# NB-IoT-ideaboard-v2_0.net
KiCad netlist of a schematic drawn in EAGLE
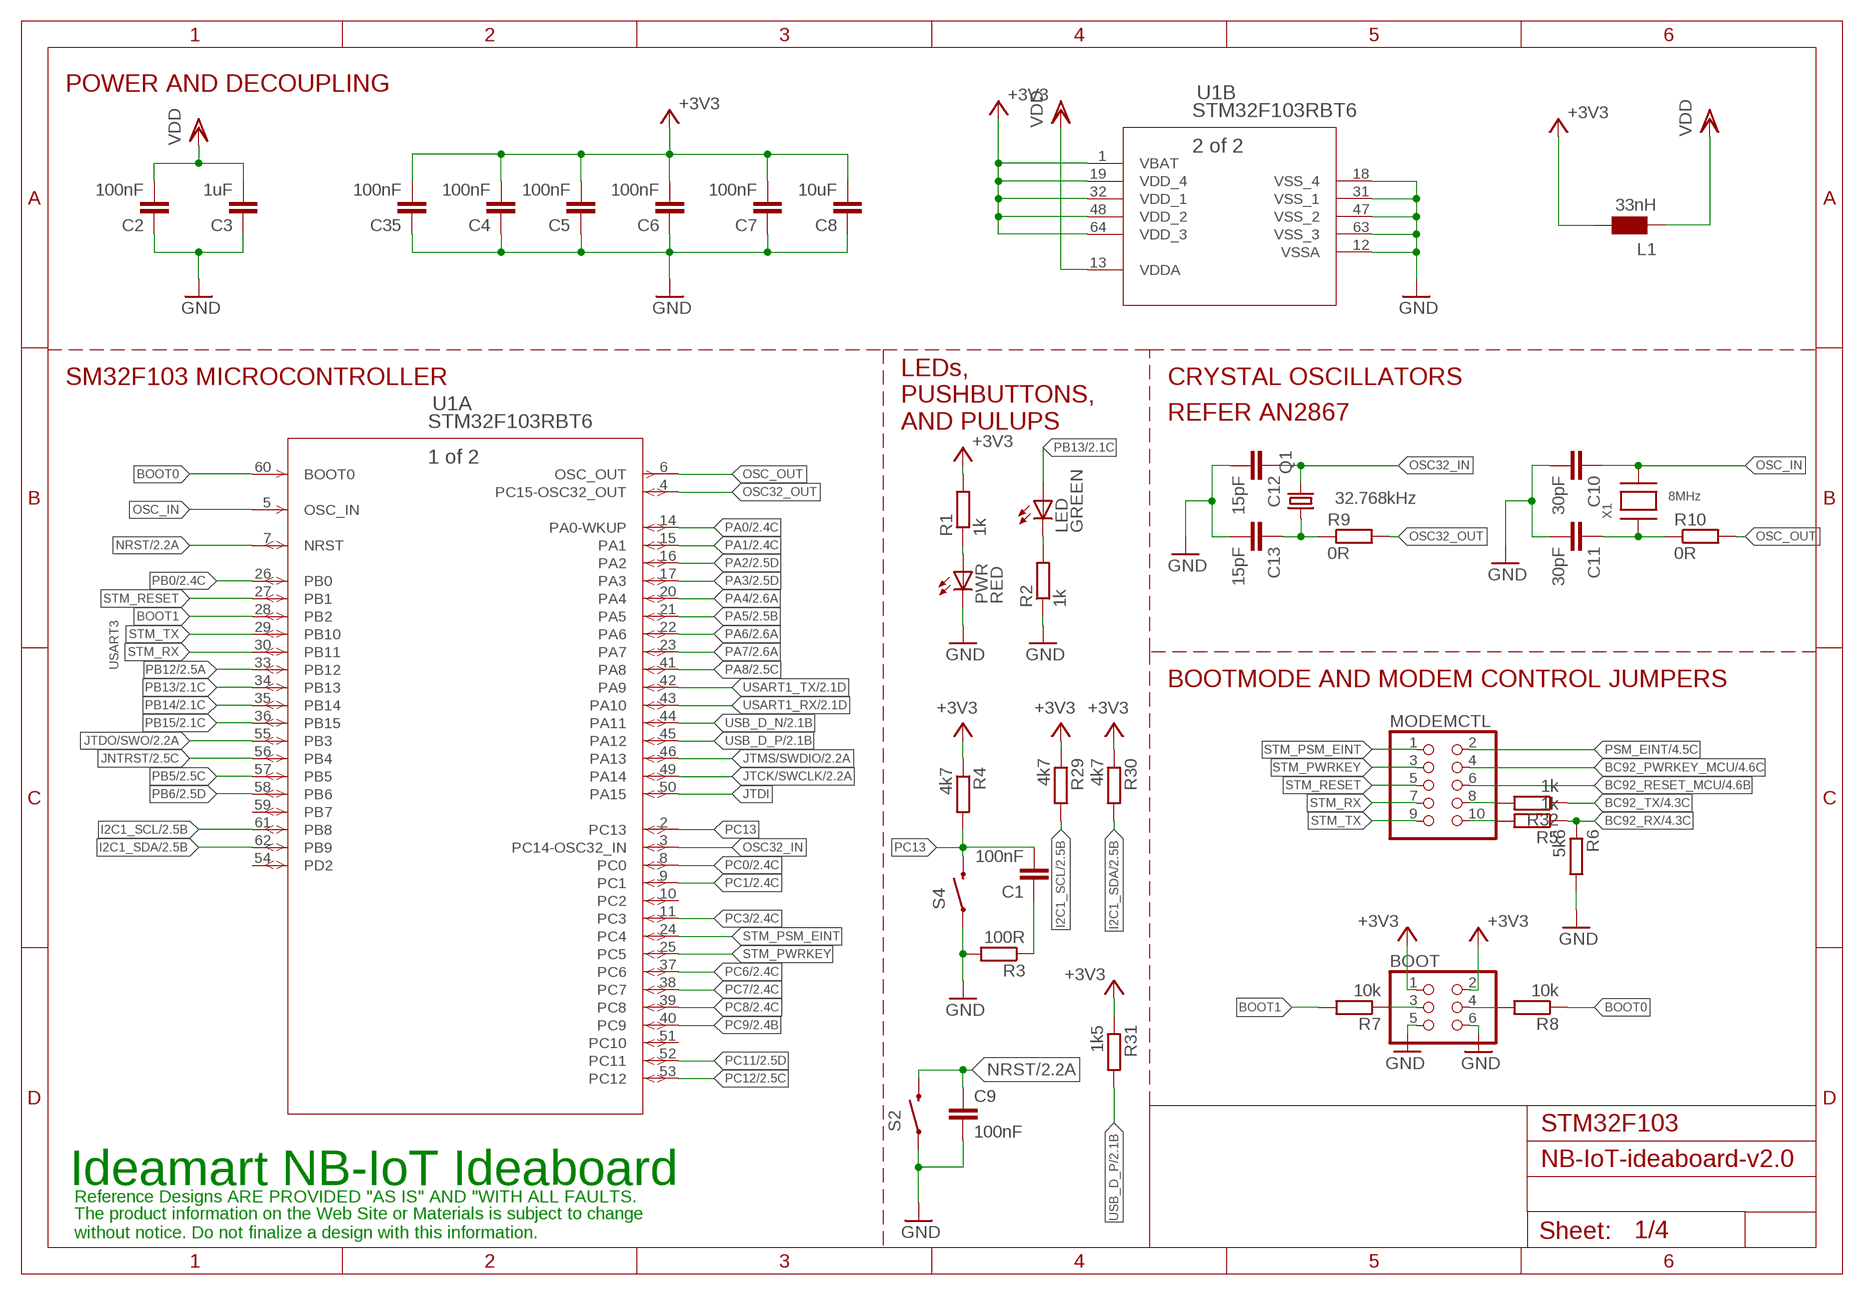
[diagram p0: schematic, sheet 1]
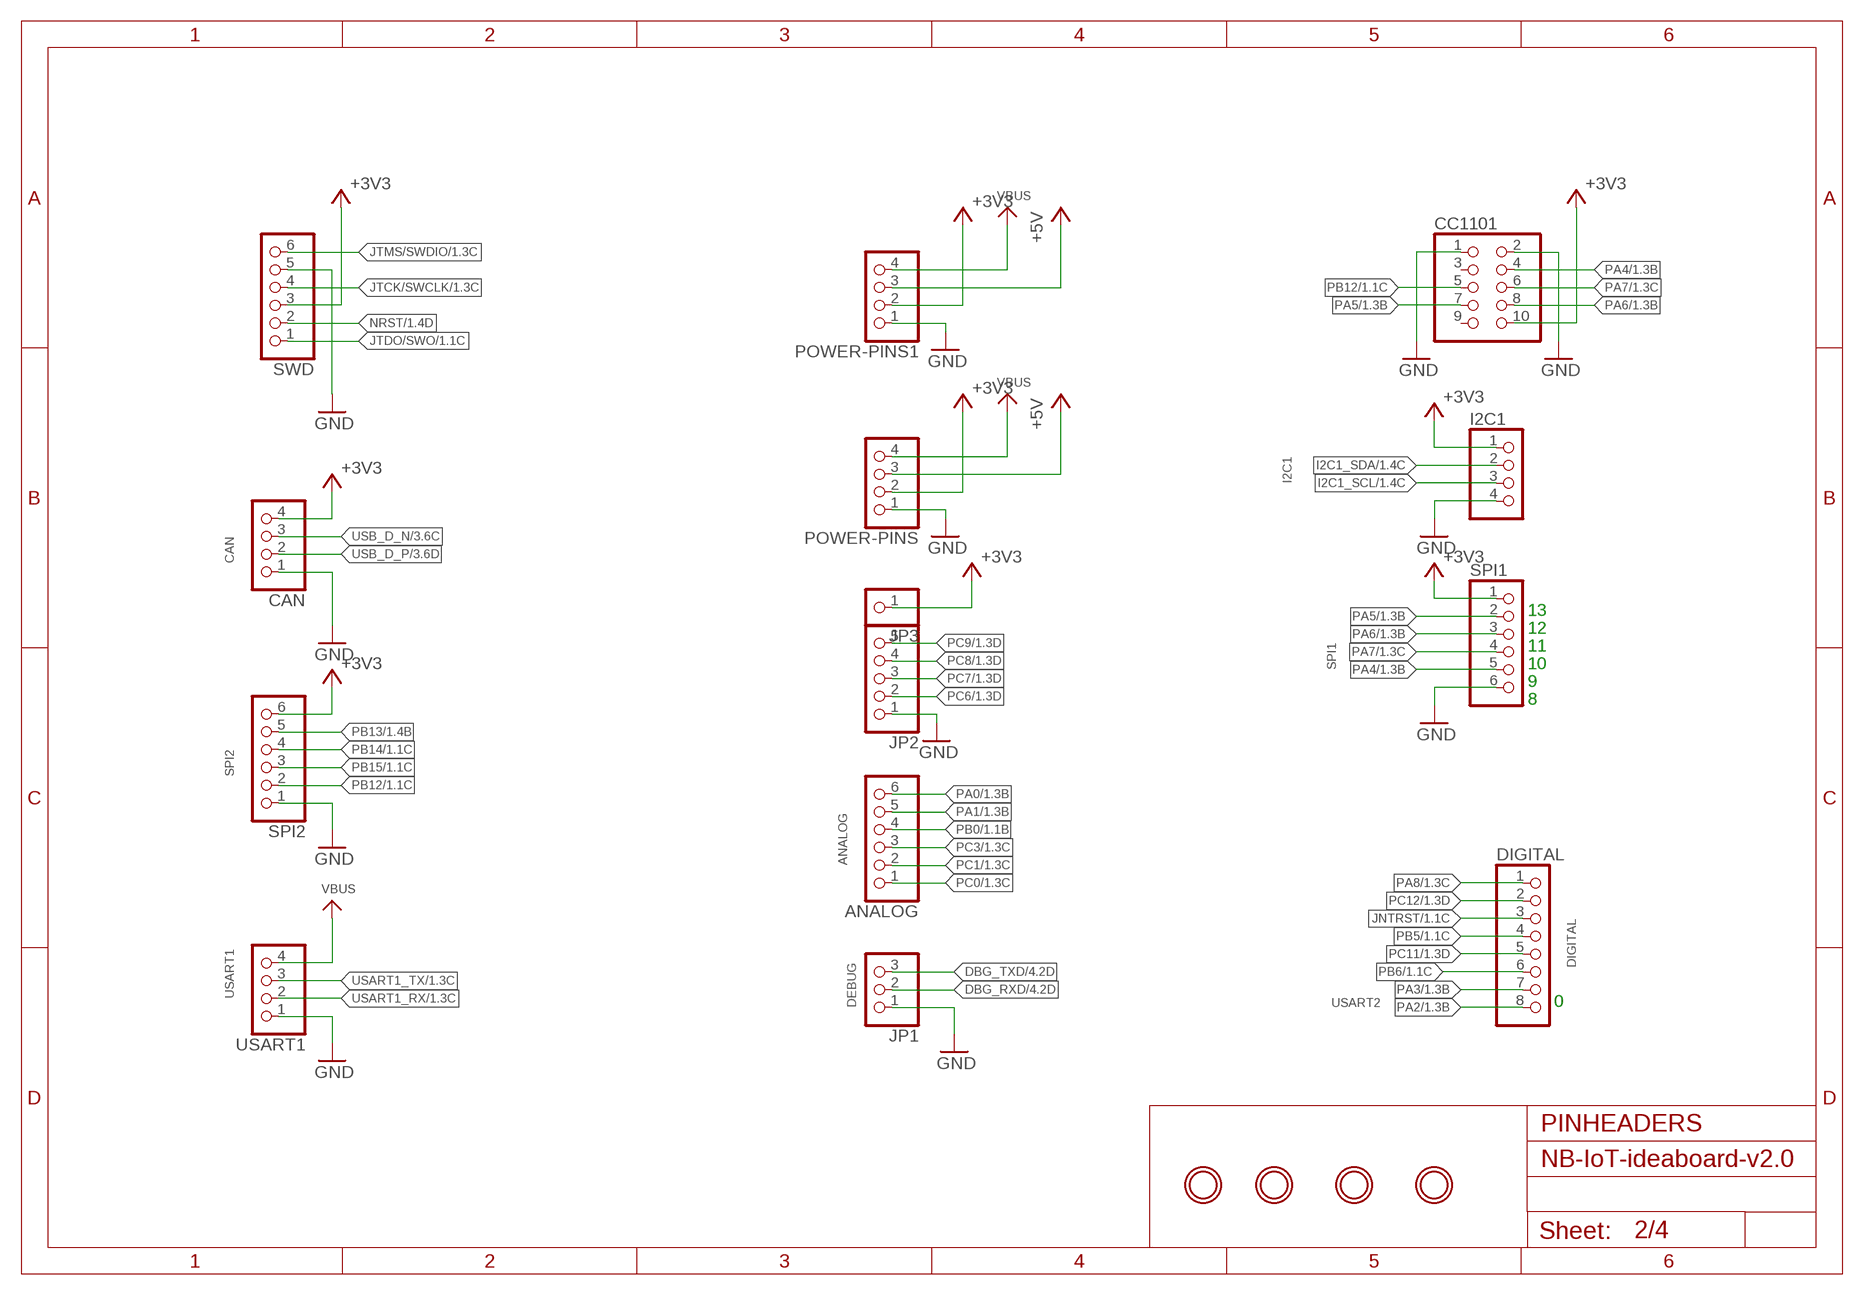
[diagram p1: schematic, sheet 2]
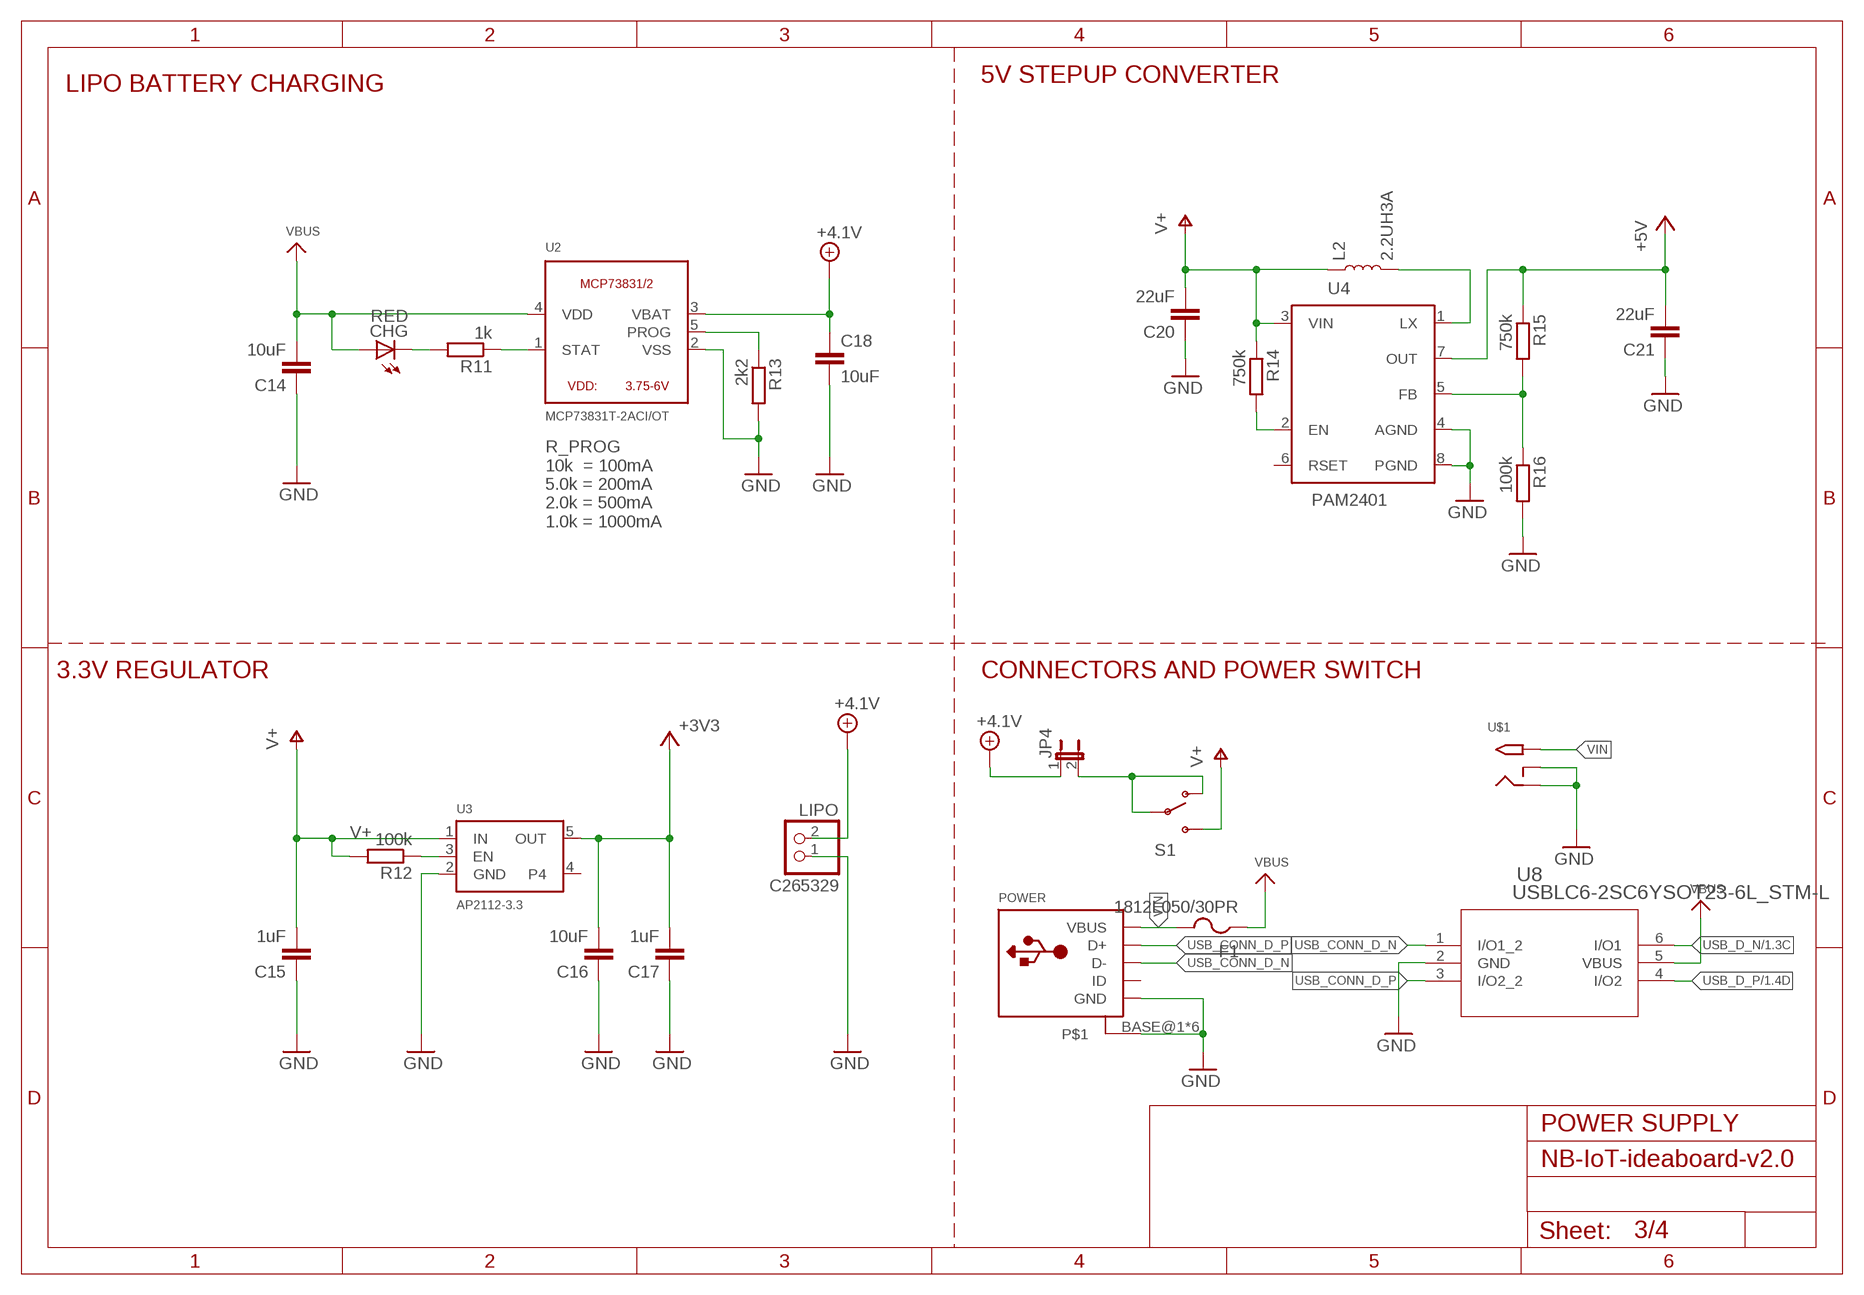
[diagram p2: schematic, sheet 3]
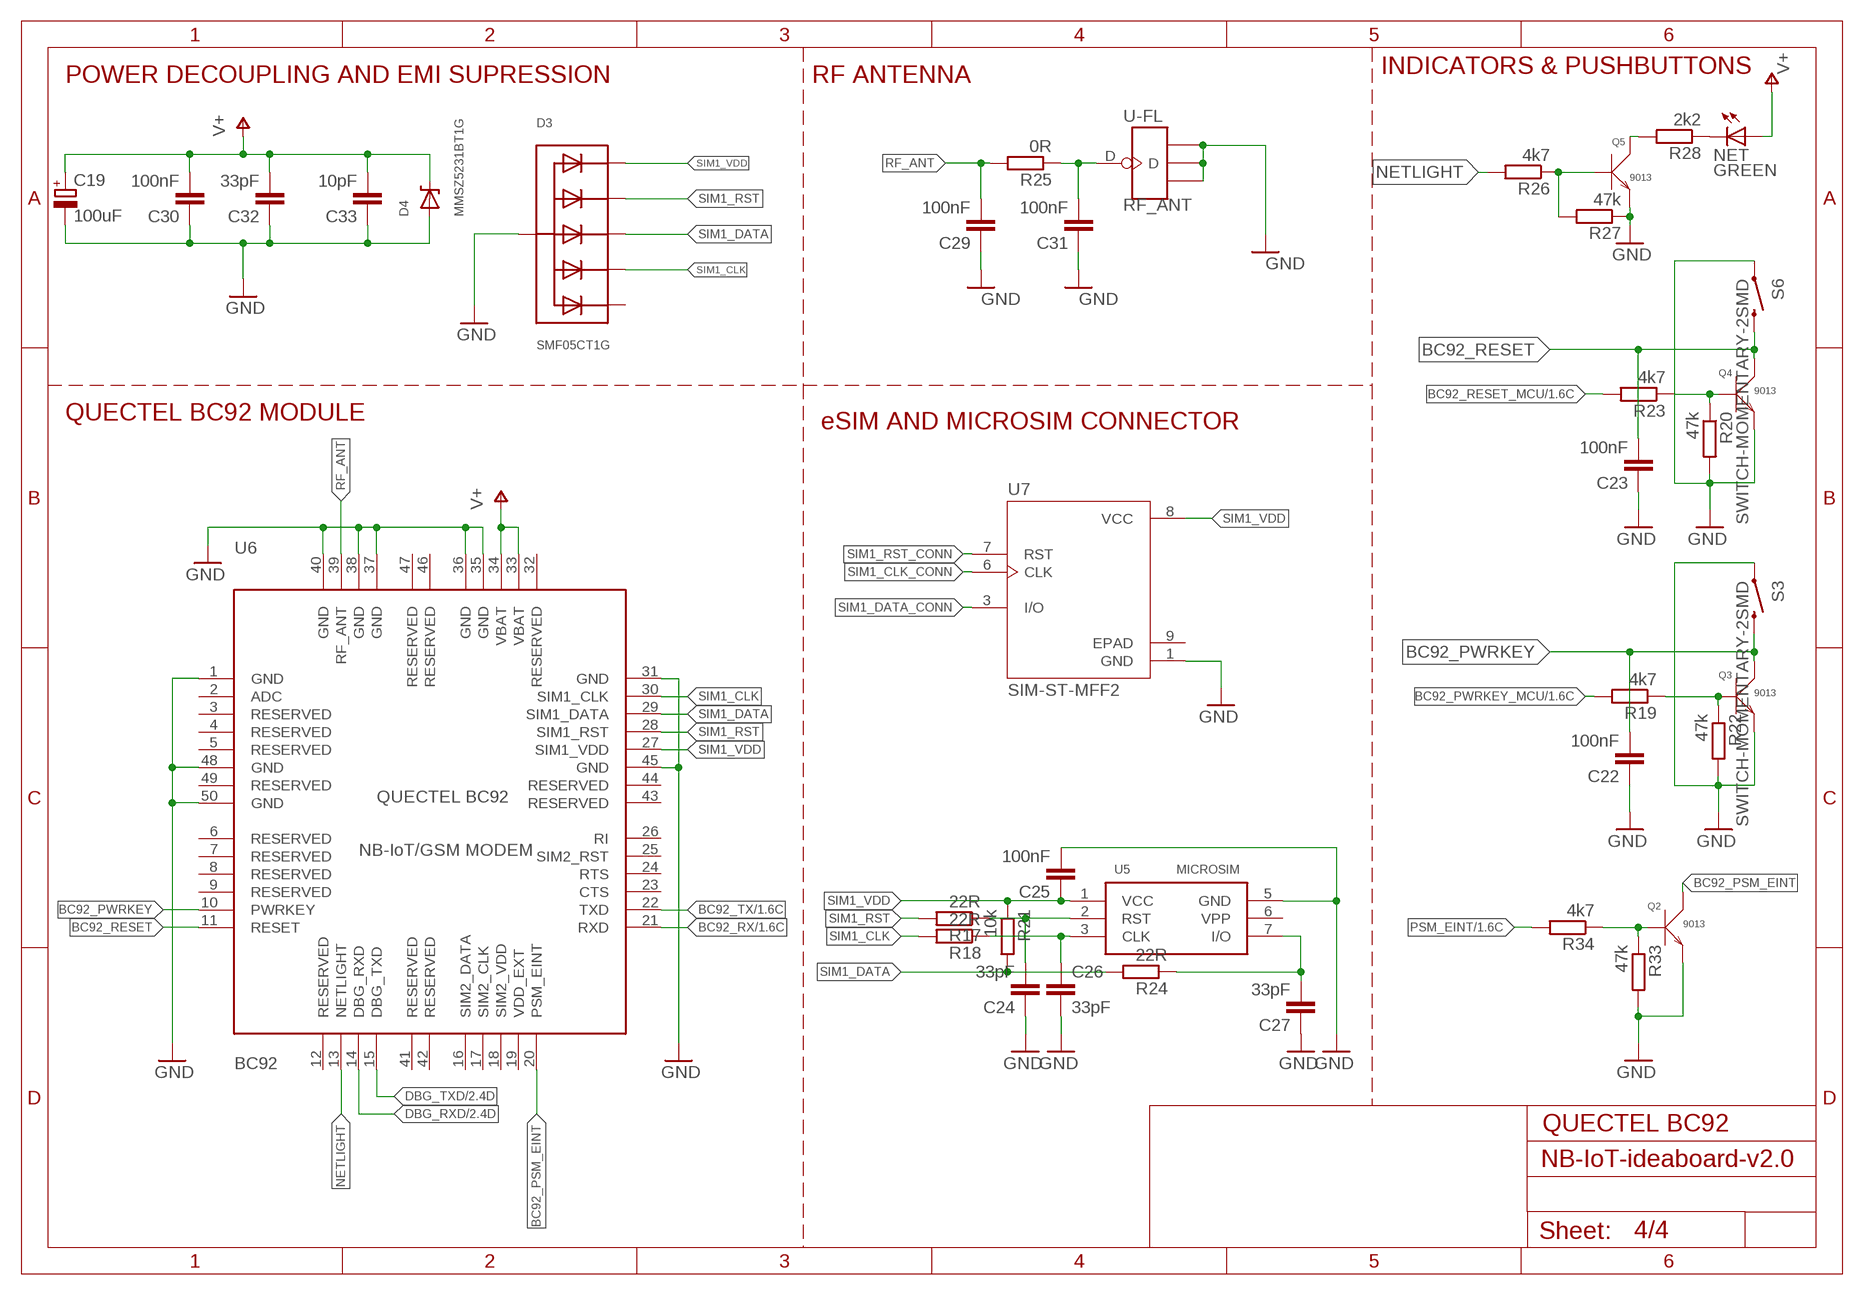
[diagram p3: schematic, sheet 4]

(export (version "E")
  (design (tool "Eeschema 10.0.6"))
  (components
    (comp (ref "BOOT")
      (value "PINHD-2X03_2.54")
      (footprint "eagle-import:2X03")
      (libsource (lib "eagle-import") (part "PINHD-2X03_2.54"))
    )
    (comp (ref "C1")
      (value "100nF")
      (footprint "eagle-import:C0805")
      (libsource (lib "eagle-import") (part "C-EUC0805"))
    )
    (comp (ref "C2")
      (value "100nF")
      (footprint "eagle-import:C0805")
      (libsource (lib "eagle-import") (part "C-EUC0805"))
    )
    (comp (ref "C3")
      (value "1uF")
      (footprint "eagle-import:C0805")
      (libsource (lib "eagle-import") (part "C-EUC0805"))
    )
    (comp (ref "C4")
      (value "100nF")
      (footprint "eagle-import:C0805")
      (libsource (lib "eagle-import") (part "C-EUC0805"))
    )
    (comp (ref "C5")
      (value "100nF")
      (footprint "eagle-import:C0805")
      (libsource (lib "eagle-import") (part "C-EUC0805"))
    )
    (comp (ref "C6")
      (value "100nF")
      (footprint "eagle-import:C0805")
      (libsource (lib "eagle-import") (part "C-EUC0805"))
    )
    (comp (ref "C7")
      (value "100nF")
      (footprint "eagle-import:C0805")
      (libsource (lib "eagle-import") (part "C-EUC0805"))
    )
    (comp (ref "C8")
      (value "10uF")
      (footprint "eagle-import:C1206")
      (libsource (lib "eagle-import") (part "C-EUC1206"))
    )
    (comp (ref "C9")
      (value "100nF")
      (footprint "eagle-import:C0805")
      (libsource (lib "eagle-import") (part "C-EUC0805"))
    )
    (comp (ref "C10")
      (value "30pF")
      (footprint "eagle-import:C0805")
      (libsource (lib "eagle-import") (part "C-EUC0805"))
    )
    (comp (ref "C11")
      (value "30pF")
      (footprint "eagle-import:C0805")
      (libsource (lib "eagle-import") (part "C-EUC0805"))
    )
    (comp (ref "C12")
      (value "15pF")
      (footprint "eagle-import:C0805")
      (libsource (lib "eagle-import") (part "C-EUC0805"))
    )
    (comp (ref "C13")
      (value "15pF")
      (footprint "eagle-import:C0805")
      (libsource (lib "eagle-import") (part "C-EUC0805"))
    )
    (comp (ref "C35")
      (value "100nF")
      (footprint "eagle-import:C0805")
      (libsource (lib "eagle-import") (part "C-EUC0805"))
    )
    (comp (ref "L1")
      (value "33nH")
      (footprint "eagle-import:0603")
      (libsource (lib "eagle-import") (part "WE-CBF_0603"))
    )
    (comp (ref "LED")
      (value "GREEN")
      (footprint "eagle-import:CHIP-LED0805")
      (libsource (lib "eagle-import") (part "LEDCHIP-LED0805"))
    )
    (comp (ref "MODEMCTL")
      (value "PINHD-2X05_2.54")
      (footprint "eagle-import:2X05")
      (libsource (lib "eagle-import") (part "PINHD-2X05_2.54"))
    )
    (comp (ref "PWR")
      (value "RED")
      (footprint "eagle-import:CHIP-LED0805")
      (libsource (lib "eagle-import") (part "LEDCHIP-LED0805"))
    )
    (comp (ref "Q1")
      (value "32.768kHz")
      (footprint "eagle-import:3.2X1.5")
      (libsource (lib "eagle-import") (part "KX-327-NHT"))
    )
    (comp (ref "R1")
      (value "1k")
      (footprint "eagle-import:R0805")
      (libsource (lib "eagle-import") (part "R-EU_R0805"))
    )
    (comp (ref "R2")
      (value "1k")
      (footprint "eagle-import:R0805")
      (libsource (lib "eagle-import") (part "R-EU_R0805"))
    )
    (comp (ref "R3")
      (value "100R")
      (footprint "eagle-import:R0805")
      (libsource (lib "eagle-import") (part "R-EU_R0805"))
    )
    (comp (ref "R4")
      (value "4k7")
      (footprint "eagle-import:R0805")
      (libsource (lib "eagle-import") (part "R-EU_R0805"))
    )
    (comp (ref "R5")
      (value "1k")
      (footprint "eagle-import:R0805")
      (libsource (lib "eagle-import") (part "R-EU_R0805"))
    )
    (comp (ref "R6")
      (value "5k6")
      (footprint "eagle-import:R0805")
      (libsource (lib "eagle-import") (part "R-EU_R0805"))
    )
    (comp (ref "R7")
      (value "10k")
      (footprint "eagle-import:R0805")
      (libsource (lib "eagle-import") (part "R-EU_R0805"))
    )
    (comp (ref "R8")
      (value "10k")
      (footprint "eagle-import:R0805")
      (libsource (lib "eagle-import") (part "R-EU_R0805"))
    )
    (comp (ref "R9")
      (value "0R")
      (footprint "eagle-import:R0805")
      (libsource (lib "eagle-import") (part "R-EU_R0805"))
    )
    (comp (ref "R10")
      (value "0R")
      (footprint "eagle-import:R0805")
      (libsource (lib "eagle-import") (part "R-EU_R0805"))
    )
    (comp (ref "R29")
      (value "4k7")
      (footprint "eagle-import:R0805")
      (libsource (lib "eagle-import") (part "R-EU_R0805"))
    )
    (comp (ref "R30")
      (value "4k7")
      (footprint "eagle-import:R0805")
      (libsource (lib "eagle-import") (part "R-EU_R0805"))
    )
    (comp (ref "R31")
      (value "1k5")
      (footprint "eagle-import:R0805")
      (libsource (lib "eagle-import") (part "R-EU_R0805"))
    )
    (comp (ref "R32")
      (value "1k")
      (footprint "eagle-import:R0805")
      (libsource (lib "eagle-import") (part "R-EU_R0805"))
    )
    (comp (ref "S2")
      (value "SWITCH-MOMENTARY-2SMD")
      (footprint "eagle-import:TACTILE-SWITCH-SMD")
      (libsource (lib "eagle-import") (part "SWITCH-MOMENTARY-2SMD"))
    )
    (comp (ref "S4")
      (value "SWITCH-MOMENTARY-2SMD")
      (footprint "eagle-import:TACTILE-SWITCH-SMD")
      (libsource (lib "eagle-import") (part "SWITCH-MOMENTARY-2SMD"))
    )
    (comp (ref "U1")
      (value "STM32F103RBT6")
      (footprint "eagle-import:LQFP64-10X10MM")
      (fields (field (name "COPYRIGHT") "Copyright (C) 2018 Accelerated Designs. All rights reserved"))
      (libsource (lib "eagle-import") (part "STM32F103RBT6"))
    )
    (comp (ref "X1")
      (value "8MHz")
      (footprint "eagle-import:NX5032")
      (libsource (lib "eagle-import") (part "XTALNX5032"))
    )
    (comp (ref "C19")
      (value "100uF")
      (footprint "eagle-import:B_3528-21R")
      (libsource (lib "eagle-import") (part "CPOL-EUB/3528-21R"))
    )
    (comp (ref "C22")
      (value "100nF")
      (footprint "eagle-import:C0805")
      (libsource (lib "eagle-import") (part "C-EUC0805"))
    )
    (comp (ref "C23")
      (value "100nF")
      (footprint "eagle-import:C0805")
      (libsource (lib "eagle-import") (part "C-EUC0805"))
    )
    (comp (ref "C24")
      (value "33pF")
      (footprint "eagle-import:C0805")
      (libsource (lib "eagle-import") (part "C-EUC0805"))
    )
    (comp (ref "C25")
      (value "100nF")
      (footprint "eagle-import:C0805")
      (libsource (lib "eagle-import") (part "C-EUC0805"))
    )
    (comp (ref "C26")
      (value "33pF")
      (footprint "eagle-import:C0805")
      (libsource (lib "eagle-import") (part "C-EUC0805"))
    )
    (comp (ref "C27")
      (value "33pF")
      (footprint "eagle-import:C0805")
      (libsource (lib "eagle-import") (part "C-EUC0805"))
    )
    (comp (ref "C29")
      (value "100nF")
      (footprint "eagle-import:C0805")
      (libsource (lib "eagle-import") (part "C-EUC0805"))
    )
    (comp (ref "C30")
      (value "100nF")
      (footprint "eagle-import:C0805")
      (libsource (lib "eagle-import") (part "C-EUC0805"))
    )
    (comp (ref "C31")
      (value "100nF")
      (footprint "eagle-import:C0805")
      (libsource (lib "eagle-import") (part "C-EUC0805"))
    )
    (comp (ref "C32")
      (value "33pF")
      (footprint "eagle-import:C0805")
      (libsource (lib "eagle-import") (part "C-EUC0805"))
    )
    (comp (ref "C33")
      (value "10pF")
      (footprint "eagle-import:C0805")
      (libsource (lib "eagle-import") (part "C-EUC0805"))
    )
    (comp (ref "D3")
      (value "SMF05CT1G")
      (footprint "eagle-import:SOT363")
      (libsource (lib "eagle-import") (part "TVSARRAY_5LANE"))
    )
    (comp (ref "D4")
      (value "MMSZ5231BT1G")
      (footprint "eagle-import:SOD-123")
      (libsource (lib "eagle-import") (part "DIODE-ZENERSOD123"))
    )
    (comp (ref "NET")
      (value "GREEN")
      (footprint "eagle-import:CHIP-LED0805")
      (libsource (lib "eagle-import") (part "LEDCHIP-LED0805"))
    )
    (comp (ref "Q2")
      (value "9013")
      (footprint "eagle-import:SOT23")
      (libsource (lib "eagle-import") (part "TRANSISTOR-NPN-SOT23"))
    )
    (comp (ref "Q3")
      (value "9013")
      (footprint "eagle-import:SOT23")
      (libsource (lib "eagle-import") (part "TRANSISTOR-NPN-SOT23"))
    )
    (comp (ref "Q4")
      (value "9013")
      (footprint "eagle-import:SOT23")
      (libsource (lib "eagle-import") (part "TRANSISTOR-NPN-SOT23"))
    )
    (comp (ref "Q5")
      (value "9013")
      (footprint "eagle-import:SOT23")
      (libsource (lib "eagle-import") (part "TRANSISTOR-NPN-SOT23"))
    )
    (comp (ref "R17")
      (value "22R")
      (footprint "eagle-import:R0805")
      (libsource (lib "eagle-import") (part "R-EU_R0805"))
    )
    (comp (ref "R18")
      (value "22R")
      (footprint "eagle-import:R0805")
      (libsource (lib "eagle-import") (part "R-EU_R0805"))
    )
    (comp (ref "R19")
      (value "4k7")
      (footprint "eagle-import:R0805")
      (libsource (lib "eagle-import") (part "R-EU_R0805"))
    )
    (comp (ref "R20")
      (value "47k")
      (footprint "eagle-import:R0805")
      (libsource (lib "eagle-import") (part "R-EU_R0805"))
    )
    (comp (ref "R21")
      (value "10k")
      (footprint "eagle-import:R0805")
      (libsource (lib "eagle-import") (part "R-EU_R0805"))
    )
    (comp (ref "R22")
      (value "47k")
      (footprint "eagle-import:R0805")
      (libsource (lib "eagle-import") (part "R-EU_R0805"))
    )
    (comp (ref "R23")
      (value "4k7")
      (footprint "eagle-import:R0805")
      (libsource (lib "eagle-import") (part "R-EU_R0805"))
    )
    (comp (ref "R24")
      (value "22R")
      (footprint "eagle-import:R0805")
      (libsource (lib "eagle-import") (part "R-EU_R0805"))
    )
    (comp (ref "R25")
      (value "0R")
      (footprint "eagle-import:R0805")
      (libsource (lib "eagle-import") (part "R-EU_R0805"))
    )
    (comp (ref "R26")
      (value "4k7")
      (footprint "eagle-import:R0805")
      (libsource (lib "eagle-import") (part "R-EU_R0805"))
    )
    (comp (ref "R27")
      (value "47k")
      (footprint "eagle-import:R0805")
      (libsource (lib "eagle-import") (part "R-EU_R0805"))
    )
    (comp (ref "R28")
      (value "2k2")
      (footprint "eagle-import:R0805")
      (libsource (lib "eagle-import") (part "R-EU_R0805"))
    )
    (comp (ref "R33")
      (value "47k")
      (footprint "eagle-import:R0805")
      (libsource (lib "eagle-import") (part "R-EU_R0805"))
    )
    (comp (ref "R34")
      (value "4k7")
      (footprint "eagle-import:R0805")
      (libsource (lib "eagle-import") (part "R-EU_R0805"))
    )
    (comp (ref "RF_ANT")
      (value "U-FL")
      (footprint "eagle-import:4P-U-FL")
      (libsource (lib "eagle-import") (part "ANTENNA-U-FL"))
    )
    (comp (ref "S3")
      (value "SWITCH-MOMENTARY-2SMD")
      (footprint "eagle-import:TACTILE-SWITCH-SMD")
      (libsource (lib "eagle-import") (part "SWITCH-MOMENTARY-2SMD"))
    )
    (comp (ref "S6")
      (value "SWITCH-MOMENTARY-2SMD")
      (footprint "eagle-import:TACTILE-SWITCH-SMD")
      (libsource (lib "eagle-import") (part "SWITCH-MOMENTARY-2SMD"))
    )
    (comp (ref "U5")
      (value "MICROSIM")
      (footprint "eagle-import:MICROSIM")
      (libsource (lib "eagle-import") (part "MICROSIM"))
    )
    (comp (ref "U6")
      (value "BC92")
      (footprint "eagle-import:BC92")
      (libsource (lib "eagle-import") (part "BC92"))
    )
    (comp (ref "U7")
      (value "SIM-ST-MFF2")
      (footprint "eagle-import:PSON127P500X600X82-9N")
      (fields (field (name "MF") "Hologram, Inc."))
      (libsource (lib "eagle-import") (part "SIM-ST-MFF2"))
    )
    (comp (ref "C14")
      (value "10uF")
      (footprint "eagle-import:C0805")
      (libsource (lib "eagle-import") (part "C-EUC0805"))
    )
    (comp (ref "C15")
      (value "1uF")
      (footprint "eagle-import:C0805")
      (libsource (lib "eagle-import") (part "C-EUC0805"))
    )
    (comp (ref "C16")
      (value "10uF")
      (footprint "eagle-import:C0805")
      (libsource (lib "eagle-import") (part "C-EUC0805"))
    )
    (comp (ref "C17")
      (value "1uF")
      (footprint "eagle-import:C0805")
      (libsource (lib "eagle-import") (part "C-EUC0805"))
    )
    (comp (ref "C18")
      (value "10uF")
      (footprint "eagle-import:C0805")
      (libsource (lib "eagle-import") (part "C-EUC0805"))
    )
    (comp (ref "C20")
      (value "22uF")
      (footprint "eagle-import:C0805")
      (libsource (lib "eagle-import") (part "C-EUC0805"))
    )
    (comp (ref "C21")
      (value "22uF")
      (footprint "eagle-import:C0805")
      (libsource (lib "eagle-import") (part "C-EUC0805"))
    )
    (comp (ref "CHG")
      (value "RED")
      (footprint "eagle-import:CHIP-LED0805")
      (libsource (lib "eagle-import") (part "LEDCHIP-LED0805"))
    )
    (comp (ref "F1")
      (value "1812L050/30PR")
      (footprint "eagle-import:1812")
      (libsource (lib "eagle-import") (part "PTCFUSE-1812"))
    )
    (comp (ref "JP4")
      (value "JP1E")
      (footprint "eagle-import:JP1")
      (libsource (lib "eagle-import") (part "JP1E"))
    )
    (comp (ref "L2")
      (value "2.2UH3A")
      (footprint "eagle-import:INDUCTOR_4X4MM")
      (libsource (lib "eagle-import") (part "INDUCTOR-IFSC1515AHER2R2M01"))
    )
    (comp (ref "LIPO")
      (value "C265329")
      (footprint "eagle-import:JST-PH-2-SMT")
      (libsource (lib "eagle-import") (part "JST_2PIN-SMT"))
    )
    (comp (ref "POWER")
      (value "USB_MICRO_20329_V2")
      (footprint "eagle-import:4UCONN_20329_V2")
      (libsource (lib "eagle-import") (part "USB_MICRO_20329_V2"))
    )
    (comp (ref "R11")
      (value "1k")
      (footprint "eagle-import:R0805")
      (libsource (lib "eagle-import") (part "R-EU_R0805"))
    )
    (comp (ref "R12")
      (value "100k")
      (footprint "eagle-import:R0805")
      (libsource (lib "eagle-import") (part "R-EU_R0805"))
    )
    (comp (ref "R13")
      (value "2k2")
      (footprint "eagle-import:R0805")
      (libsource (lib "eagle-import") (part "R-EU_R0805"))
    )
    (comp (ref "R14")
      (value "750k")
      (footprint "eagle-import:R0805")
      (libsource (lib "eagle-import") (part "R-EU_R0805"))
    )
    (comp (ref "R15")
      (value "750k")
      (footprint "eagle-import:R0805")
      (libsource (lib "eagle-import") (part "R-EU_R0805"))
    )
    (comp (ref "R16")
      (value "100k")
      (footprint "eagle-import:R0805")
      (libsource (lib "eagle-import") (part "R-EU_R0805"))
    )
    (comp (ref "S1")
      (value "SWITCH-SPDT-SMD-A")
      (footprint "eagle-import:SWITCH-SPST-SMD-A")
      (libsource (lib "eagle-import") (part "SWITCH-SPDT-SMD-A"))
    )
    (comp (ref "U$1")
      (value "2.1MMJACKSMT")
      (footprint "eagle-import:DCJACK_2MM_SMT")
      (libsource (lib "eagle-import") (part "2.1MMJACKSMT"))
    )
    (comp (ref "U2")
      (value "MCP73831T-2ACI/OT")
      (footprint "eagle-import:SOT23-5")
      (libsource (lib "eagle-import") (part "MCP73831/2"))
    )
    (comp (ref "U3")
      (value "AP2112-3.3")
      (footprint "eagle-import:SOT23-5")
      (libsource (lib "eagle-import") (part "VREG_SOT23-5"))
    )
    (comp (ref "U4")
      (value "PAM2401")
      (footprint "eagle-import:MSOP8")
      (libsource (lib "eagle-import") (part "PAM2401"))
    )
    (comp (ref "U8")
      (value "USBLC6-2SC6YSOT23-6L_STM-L")
      (footprint "eagle-import:SOT23-6L_STM-L")
      (fields (field (name "MANUFACTURER_PART_NUMBER") "USBLC6-2SC6Y"))
      (libsource (lib "eagle-import") (part "USBLC6-2SC6YSOT23-6L_STM-L"))
    )
    (comp (ref "$H1")
      (value "MOUNTINGHOLE3.0THIN")
      (footprint "eagle-import:MOUNTINGHOLE_3.0_PLATEDTHIN")
      (libsource (lib "eagle-import") (part "MOUNTINGHOLE3.0THIN"))
    )
    (comp (ref "$H2")
      (value "MOUNTINGHOLE3.0THIN")
      (footprint "eagle-import:MOUNTINGHOLE_3.0_PLATEDTHIN")
      (libsource (lib "eagle-import") (part "MOUNTINGHOLE3.0THIN"))
    )
    (comp (ref "$H3")
      (value "MOUNTINGHOLE3.0THIN")
      (footprint "eagle-import:MOUNTINGHOLE_3.0_PLATEDTHIN")
      (libsource (lib "eagle-import") (part "MOUNTINGHOLE3.0THIN"))
    )
    (comp (ref "$H4")
      (value "MOUNTINGHOLE3.0THIN")
      (footprint "eagle-import:MOUNTINGHOLE_3.0_PLATEDTHIN")
      (libsource (lib "eagle-import") (part "MOUNTINGHOLE3.0THIN"))
    )
    (comp (ref "ANALOG")
      (value "PINHD-1X06_2.54-S")
      (footprint "eagle-import:1X06-S")
      (libsource (lib "eagle-import") (part "PINHD-1X06_2.54-S"))
    )
    (comp (ref "CAN")
      (value "PINHD-1X04_2.54-S")
      (footprint "eagle-import:1X04-S")
      (libsource (lib "eagle-import") (part "PINHD-1X04_2.54-S"))
    )
    (comp (ref "CC1101")
      (value "PINHD-2X05_2.54")
      (footprint "eagle-import:2X05")
      (libsource (lib "eagle-import") (part "PINHD-2X05_2.54"))
    )
    (comp (ref "DIGITAL")
      (value "PINHD-1X08_2.54-S")
      (footprint "eagle-import:1X08-S")
      (libsource (lib "eagle-import") (part "PINHD-1X08_2.54-S"))
    )
    (comp (ref "I2C1")
      (value "PINHD-1X04_2.54-S")
      (footprint "eagle-import:1X04-S")
      (libsource (lib "eagle-import") (part "PINHD-1X04_2.54-S"))
    )
    (comp (ref "JP1")
      (value "PINHD-1X03_2.54-S")
      (footprint "eagle-import:1X03-S")
      (libsource (lib "eagle-import") (part "PINHD-1X03_2.54-S"))
    )
    (comp (ref "JP2")
      (value "PINHD-1X05_2.54-S")
      (footprint "eagle-import:1X05-S")
      (libsource (lib "eagle-import") (part "PINHD-1X05_2.54-S"))
    )
    (comp (ref "JP3")
      (value "PINHD-1X01_2.54-S")
      (footprint "eagle-import:1X01-S")
      (libsource (lib "eagle-import") (part "PINHD-1X01_2.54-S"))
    )
    (comp (ref "POWER-PINS")
      (value "PINHD-1X04_2.54-S")
      (footprint "eagle-import:1X04-S")
      (libsource (lib "eagle-import") (part "PINHD-1X04_2.54-S"))
    )
    (comp (ref "POWER-PINS1")
      (value "PINHD-1X04_2.54-S")
      (footprint "eagle-import:1X04-S")
      (libsource (lib "eagle-import") (part "PINHD-1X04_2.54-S"))
    )
    (comp (ref "SPI1")
      (value "PINHD-1X06_2.54-S")
      (footprint "eagle-import:1X06-S")
      (libsource (lib "eagle-import") (part "PINHD-1X06_2.54-S"))
    )
    (comp (ref "SPI2")
      (value "PINHD-1X06_2.54-S")
      (footprint "eagle-import:1X06-S")
      (libsource (lib "eagle-import") (part "PINHD-1X06_2.54-S"))
    )
    (comp (ref "SWD")
      (value "PINHD-1X06_2.54-S")
      (footprint "eagle-import:1X06-S")
      (libsource (lib "eagle-import") (part "PINHD-1X06_2.54-S"))
    )
    (comp (ref "USART1")
      (value "PINHD-1X04_2.54-S")
      (footprint "eagle-import:1X04-S")
      (libsource (lib "eagle-import") (part "PINHD-1X04_2.54-S"))
    )
  )
  (nets
    (net (code "1") (name "+3V3") (class "Default")
      (node (ref "BOOT") (pin "1") (pinfunction "1_1") (pintype "passive"))
      (node (ref "BOOT") (pin "2") (pinfunction "2_2") (pintype "passive"))
      (node (ref "C16") (pin "2") (pinfunction "2_2") (pintype "passive"))
      (node (ref "C17") (pin "2") (pinfunction "2_2") (pintype "passive"))
      (node (ref "C35") (pin "2") (pinfunction "2_2") (pintype "passive"))
      (node (ref "C4") (pin "2") (pinfunction "2_2") (pintype "passive"))
      (node (ref "C5") (pin "2") (pinfunction "2_2") (pintype "passive"))
      (node (ref "C6") (pin "2") (pinfunction "2_2") (pintype "passive"))
      (node (ref "C7") (pin "2") (pinfunction "2_2") (pintype "passive"))
      (node (ref "C8") (pin "2") (pinfunction "2_2") (pintype "passive"))
      (node (ref "CAN") (pin "4") (pinfunction "4_4") (pintype "passive"))
      (node (ref "CC1101") (pin "10") (pinfunction "10_10") (pintype "passive"))
      (node (ref "I2C1") (pin "1") (pinfunction "1_1") (pintype "passive"))
      (node (ref "JP3") (pin "1") (pinfunction "1_1") (pintype "passive"))
      (node (ref "L1") (pin "2") (pinfunction "2_2") (pintype "passive"))
      (node (ref "POWER-PINS") (pin "2") (pinfunction "2_2") (pintype "passive"))
      (node (ref "POWER-PINS1") (pin "2") (pinfunction "2_2") (pintype "passive"))
      (node (ref "R1") (pin "2") (pinfunction "2_2") (pintype "passive"))
      (node (ref "R29") (pin "1") (pinfunction "1_1") (pintype "passive"))
      (node (ref "R30") (pin "1") (pinfunction "1_1") (pintype "passive"))
      (node (ref "R31") (pin "1") (pinfunction "1_1") (pintype "passive"))
      (node (ref "R4") (pin "1") (pinfunction "1_1") (pintype "passive"))
      (node (ref "SPI1") (pin "1") (pinfunction "1_1") (pintype "passive"))
      (node (ref "SPI2") (pin "6") (pinfunction "6_6") (pintype "passive"))
      (node (ref "SWD") (pin "3") (pinfunction "3_3") (pintype "passive"))
      (node (ref "U1") (pin "1") (pinfunction "VBAT_1") (pintype "power_in"))
      (node (ref "U1") (pin "19") (pinfunction "VDD_4_19") (pintype "power_in"))
      (node (ref "U1") (pin "32") (pinfunction "VDD_1_32") (pintype "power_in"))
      (node (ref "U1") (pin "48") (pinfunction "VDD_2_48") (pintype "power_in"))
      (node (ref "U1") (pin "64") (pinfunction "VDD_3_64") (pintype "power_in"))
      (node (ref "U3") (pin "5") (pinfunction "OUT_5") (pintype "power_in"))
    )
    (net (code "2") (name "+4.1V") (class "Default")
      (node (ref "C18") (pin "1") (pinfunction "1_1") (pintype "passive"))
      (node (ref "JP4") (pin "1") (pinfunction "1_1") (pintype "passive"))
      (node (ref "LIPO") (pin "2") (pinfunction "1_2") (pintype "passive"))
      (node (ref "U2") (pin "3") (pinfunction "VBAT_3") (pintype "power_in"))
    )
    (net (code "3") (name "+5V") (class "Default")
      (node (ref "C21") (pin "2") (pinfunction "2_2") (pintype "passive"))
      (node (ref "POWER-PINS") (pin "3") (pinfunction "3_3") (pintype "passive"))
      (node (ref "POWER-PINS1") (pin "3") (pinfunction "3_3") (pintype "passive"))
      (node (ref "R15") (pin "1") (pinfunction "1_1") (pintype "passive"))
      (node (ref "U4") (pin "7") (pinfunction "OUT_7") (pintype "bidirectional"))
    )
    (net (code "4") (name "BC92_PSM_EINT") (class "Default")
      (node (ref "Q2") (pin "3") (pinfunction "C_3") (pintype "passive"))
      (node (ref "U6") (pin "20") (pinfunction "PSM_EINT_20") (pintype "bidirectional"))
    )
    (net (code "5") (name "BC92_PWRKEY") (class "Default")
      (node (ref "C22") (pin "2") (pinfunction "2_2") (pintype "passive"))
      (node (ref "Q3") (pin "3") (pinfunction "C_3") (pintype "passive"))
      (node (ref "S3") (pin "3") (pinfunction "2_3") (pintype "passive"))
      (node (ref "U6") (pin "10") (pinfunction "PWRKEY_10") (pintype "bidirectional"))
    )
    (net (code "6") (name "BC92_PWRKEY_MCU") (class "Default")
      (node (ref "MODEMCTL") (pin "4") (pinfunction "4_4") (pintype "passive"))
      (node (ref "R19") (pin "2") (pinfunction "2_2") (pintype "passive"))
    )
    (net (code "7") (name "BC92_RESET") (class "Default")
      (node (ref "C23") (pin "2") (pinfunction "2_2") (pintype "passive"))
      (node (ref "Q4") (pin "3") (pinfunction "C_3") (pintype "passive"))
      (node (ref "S6") (pin "3") (pinfunction "2_3") (pintype "passive"))
      (node (ref "U6") (pin "11") (pinfunction "RESET_11") (pintype "bidirectional"))
    )
    (net (code "8") (name "BC92_RESET_MCU") (class "Default")
      (node (ref "MODEMCTL") (pin "6") (pinfunction "6_6") (pintype "passive"))
      (node (ref "R23") (pin "2") (pinfunction "2_2") (pintype "passive"))
    )
    (net (code "9") (name "BC92_RX") (class "Default")
      (node (ref "R5") (pin "1") (pinfunction "1_1") (pintype "passive"))
      (node (ref "R6") (pin "1") (pinfunction "1_1") (pintype "passive"))
      (node (ref "U6") (pin "21") (pinfunction "RXD_21") (pintype "bidirectional"))
    )
    (net (code "10") (name "BC92_TX") (class "Default")
      (node (ref "R32") (pin "1") (pinfunction "1_1") (pintype "passive"))
      (node (ref "U6") (pin "22") (pinfunction "TXD_22") (pintype "bidirectional"))
    )
    (net (code "11") (name "BOOT0") (class "Default")
      (node (ref "R8") (pin "1") (pinfunction "1_1") (pintype "passive"))
      (node (ref "U1") (pin "60") (pinfunction "BOOT0_60") (pintype "input"))
    )
    (net (code "12") (name "BOOT1") (class "Default")
      (node (ref "R7") (pin "2") (pinfunction "2_2") (pintype "passive"))
      (node (ref "U1") (pin "28") (pinfunction "PB2_28") (pintype "bidirectional"))
    )
    (net (code "13") (name "DBG_RXD") (class "Default")
      (node (ref "JP1") (pin "2") (pinfunction "2_2") (pintype "passive"))
      (node (ref "U6") (pin "14") (pinfunction "DBG_RXD_14") (pintype "bidirectional"))
    )
    (net (code "14") (name "DBG_TXD") (class "Default")
      (node (ref "JP1") (pin "3") (pinfunction "3_3") (pintype "passive"))
      (node (ref "U6") (pin "15") (pinfunction "DBG_TXD_15") (pintype "bidirectional"))
    )
    (net (code "15") (name "GND") (class "Default")
      (node (ref "BOOT") (pin "5") (pinfunction "5_5") (pintype "passive"))
      (node (ref "BOOT") (pin "6") (pinfunction "6_6") (pintype "passive"))
      (node (ref "C10") (pin "2") (pinfunction "2_2") (pintype "passive"))
      (node (ref "C11") (pin "2") (pinfunction "2_2") (pintype "passive"))
      (node (ref "C12") (pin "2") (pinfunction "2_2") (pintype "passive"))
      (node (ref "C13") (pin "2") (pinfunction "2_2") (pintype "passive"))
      (node (ref "C14") (pin "1") (pinfunction "1_1") (pintype "passive"))
      (node (ref "C15") (pin "1") (pinfunction "1_1") (pintype "passive"))
      (node (ref "C16") (pin "1") (pinfunction "1_1") (pintype "passive"))
      (node (ref "C17") (pin "1") (pinfunction "1_1") (pintype "passive"))
      (node (ref "C18") (pin "2") (pinfunction "2_2") (pintype "passive"))
      (node (ref "C19") (pin "-") (pinfunction "-_-") (pintype "passive"))
      (node (ref "C2") (pin "1") (pinfunction "1_1") (pintype "passive"))
      (node (ref "C20") (pin "1") (pinfunction "1_1") (pintype "passive"))
      (node (ref "C21") (pin "1") (pinfunction "1_1") (pintype "passive"))
      (node (ref "C22") (pin "1") (pinfunction "1_1") (pintype "passive"))
      (node (ref "C23") (pin "1") (pinfunction "1_1") (pintype "passive"))
      (node (ref "C24") (pin "1") (pinfunction "1_1") (pintype "passive"))
      (node (ref "C25") (pin "2") (pinfunction "2_2") (pintype "passive"))
      (node (ref "C26") (pin "2") (pinfunction "2_2") (pintype "passive"))
      (node (ref "C27") (pin "1") (pinfunction "1_1") (pintype "passive"))
      (node (ref "C29") (pin "1") (pinfunction "1_1") (pintype "passive"))
      (node (ref "C3") (pin "1") (pinfunction "1_1") (pintype "passive"))
      (node (ref "C30") (pin "1") (pinfunction "1_1") (pintype "passive"))
      (node (ref "C31") (pin "1") (pinfunction "1_1") (pintype "passive"))
      (node (ref "C32") (pin "1") (pinfunction "1_1") (pintype "passive"))
      (node (ref "C33") (pin "1") (pinfunction "1_1") (pintype "passive"))
      (node (ref "C35") (pin "1") (pinfunction "1_1") (pintype "passive"))
      (node (ref "C4") (pin "1") (pinfunction "1_1") (pintype "passive"))
      (node (ref "C5") (pin "1") (pinfunction "1_1") (pintype "passive"))
      (node (ref "C6") (pin "1") (pinfunction "1_1") (pintype "passive"))
      (node (ref "C7") (pin "1") (pinfunction "1_1") (pintype "passive"))
      (node (ref "C8") (pin "1") (pinfunction "1_1") (pintype "passive"))
      (node (ref "C9") (pin "2") (pinfunction "2_2") (pintype "passive"))
      (node (ref "CAN") (pin "1") (pinfunction "1_1") (pintype "passive"))
      (node (ref "CC1101") (pin "1") (pinfunction "1_1") (pintype "passive"))
      (node (ref "CC1101") (pin "2") (pinfunction "2_2") (pintype "passive"))
      (node (ref "D3") (pin "2") (pinfunction "A_2") (pintype "passive"))
      (node (ref "D4") (pin "A") (pinfunction "A_A") (pintype "passive"))
      (node (ref "I2C1") (pin "4") (pinfunction "4_4") (pintype "passive"))
      (node (ref "JP1") (pin "1") (pinfunction "1_1") (pintype "passive"))
      (node (ref "JP2") (pin "1") (pinfunction "1_1") (pintype "passive"))
      (node (ref "LIPO") (pin "1") (pinfunction "2_1") (pintype "passive"))
      (node (ref "POWER") (pin "BASE@1") (pinfunction "P$1_BASE@1") (pintype "bidirectional"))
      (node (ref "POWER") (pin "BASE@2") (pinfunction "P$1_BASE@2") (pintype "bidirectional"))
      (node (ref "POWER") (pin "GND") (pinfunction "GND_GND") (pintype "power_in"))
      (node (ref "POWER") (pin "SPRT@1") (pinfunction "P$1_SPRT@1") (pintype "bidirectional"))
      (node (ref "POWER") (pin "SPRT@2") (pinfunction "P$1_SPRT@2") (pintype "bidirectional"))
      (node (ref "POWER") (pin "SPRT@3") (pinfunction "P$1_SPRT@3") (pintype "bidirectional"))
      (node (ref "POWER") (pin "SPRT@4") (pinfunction "P$1_SPRT@4") (pintype "bidirectional"))
      (node (ref "POWER-PINS") (pin "1") (pinfunction "1_1") (pintype "passive"))
      (node (ref "POWER-PINS1") (pin "1") (pinfunction "1_1") (pintype "passive"))
      (node (ref "PWR") (pin "C") (pinfunction "C_C") (pintype "passive"))
      (node (ref "Q2") (pin "2") (pinfunction "E_2") (pintype "passive"))
      (node (ref "Q3") (pin "2") (pinfunction "E_2") (pintype "passive"))
      (node (ref "Q4") (pin "2") (pinfunction "E_2") (pintype "passive"))
      (node (ref "Q5") (pin "2") (pinfunction "E_2") (pintype "passive"))
      (node (ref "R13") (pin "2") (pinfunction "2_2") (pintype "passive"))
      (node (ref "R16") (pin "2") (pinfunction "2_2") (pintype "passive"))
      (node (ref "R2") (pin "1") (pinfunction "1_1") (pintype "passive"))
      (node (ref "R20") (pin "2") (pinfunction "2_2") (pintype "passive"))
      (node (ref "R22") (pin "2") (pinfunction "2_2") (pintype "passive"))
      (node (ref "R27") (pin "1") (pinfunction "1_1") (pintype "passive"))
      (node (ref "R3") (pin "2") (pinfunction "2_2") (pintype "passive"))
      (node (ref "R33") (pin "2") (pinfunction "2_2") (pintype "passive"))
      (node (ref "R6") (pin "2") (pinfunction "2_2") (pintype "passive"))
      (node (ref "RF_ANT") (pin "GND1") (pinfunction "GND1_GND1") (pintype "bidirectional"))
      (node (ref "RF_ANT") (pin "GND2") (pinfunction "GND2_GND2") (pintype "bidirectional"))
      (node (ref "RF_ANT") (pin "GND3") (pinfunction "GND3_GND3") (pintype "bidirectional"))
      (node (ref "S2") (pin "1") (pinfunction "1_1") (pintype "passive"))
      (node (ref "S3") (pin "1") (pinfunction "1_1") (pintype "passive"))
      (node (ref "S4") (pin "1") (pinfunction "1_1") (pintype "passive"))
      (node (ref "S6") (pin "1") (pinfunction "1_1") (pintype "passive"))
      (node (ref "SPI1") (pin "6") (pinfunction "6_6") (pintype "passive"))
      (node (ref "SPI2") (pin "1") (pinfunction "1_1") (pintype "passive"))
      (node (ref "SWD") (pin "5") (pinfunction "5_5") (pintype "passive"))
      (node (ref "U$1") (pin "GND") (pinfunction "RING_GND") (pintype "bidirectional"))
      (node (ref "U$1") (pin "GNDBREAK") (pinfunction "RING_SW_GNDBREAK") (pintype "bidirectional"))
      (node (ref "U1") (pin "12") (pinfunction "VSSA_12") (pintype "power_in"))
      (node (ref "U1") (pin "18") (pinfunction "VSS_4_18") (pintype "power_in"))
      (node (ref "U1") (pin "31") (pinfunction "VSS_1_31") (pintype "power_in"))
      (node (ref "U1") (pin "47") (pinfunction "VSS_2_47") (pintype "power_in"))
      (node (ref "U1") (pin "63") (pinfunction "VSS_3_63") (pintype "power_in"))
      (node (ref "U2") (pin "2") (pinfunction "VSS_2") (pintype "power_in"))
      (node (ref "U3") (pin "2") (pinfunction "GND_2") (pintype "power_in"))
      (node (ref "U4") (pin "4") (pinfunction "AGND_4") (pintype "bidirectional"))
      (node (ref "U4") (pin "8") (pinfunction "PGND_8") (pintype "bidirectional"))
      (node (ref "U5") (pin "5") (pinfunction "GND_5") (pintype "bidirectional"))
      (node (ref "U6") (pin "1") (pinfunction "GND_1") (pintype "bidirectional"))
      (node (ref "U6") (pin "31") (pinfunction "GND_31") (pintype "bidirectional"))
      (node (ref "U6") (pin "35") (pinfunction "GND_35") (pintype "bidirectional"))
      (node (ref "U6") (pin "36") (pinfunction "GND_36") (pintype "bidirectional"))
      (node (ref "U6") (pin "37") (pinfunction "GND_37") (pintype "bidirectional"))
      (node (ref "U6") (pin "38") (pinfunction "GND_38") (pintype "bidirectional"))
      (node (ref "U6") (pin "40") (pinfunction "GND_40") (pintype "bidirectional"))
      (node (ref "U6") (pin "45") (pinfunction "GND_45") (pintype "bidirectional"))
      (node (ref "U6") (pin "48") (pinfunction "GND_48") (pintype "bidirectional"))
      (node (ref "U6") (pin "50") (pinfunction "GND_50") (pintype "bidirectional"))
      (node (ref "U7") (pin "1") (pinfunction "GND_1") (pintype "power_in"))
      (node (ref "U8") (pin "2") (pinfunction "GND_2") (pintype "power_in"))
      (node (ref "USART1") (pin "1") (pinfunction "1_1") (pintype "passive"))
    )
    (net (code "16") (name "I2C1_SCL") (class "Default")
      (node (ref "I2C1") (pin "3") (pinfunction "3_3") (pintype "passive"))
      (node (ref "R29") (pin "2") (pinfunction "2_2") (pintype "passive"))
      (node (ref "U1") (pin "61") (pinfunction "PB8_61") (pintype "bidirectional"))
    )
    (net (code "17") (name "I2C1_SDA") (class "Default")
      (node (ref "I2C1") (pin "2") (pinfunction "2_2") (pintype "passive"))
      (node (ref "R30") (pin "2") (pinfunction "2_2") (pintype "passive"))
      (node (ref "U1") (pin "62") (pinfunction "PB9_62") (pintype "bidirectional"))
    )
    (net (code "18") (name "JNTRST") (class "Default")
      (node (ref "DIGITAL") (pin "3") (pinfunction "3_3") (pintype "passive"))
      (node (ref "U1") (pin "56") (pinfunction "PB4_56") (pintype "bidirectional"))
    )
    (net (code "19") (name "JTCK{slash}SWCLK") (class "Default")
      (node (ref "SWD") (pin "4") (pinfunction "4_4") (pintype "passive"))
      (node (ref "U1") (pin "49") (pinfunction "PA14_49") (pintype "bidirectional"))
    )
    (net (code "20") (name "JTDI") (class "Default")
      (node (ref "U1") (pin "50") (pinfunction "PA15_50") (pintype "bidirectional"))
    )
    (net (code "21") (name "JTDO{slash}SWO") (class "Default")
      (node (ref "SWD") (pin "1") (pinfunction "1_1") (pintype "passive"))
      (node (ref "U1") (pin "55") (pinfunction "PB3_55") (pintype "bidirectional"))
    )
    (net (code "22") (name "JTMS{slash}SWDIO") (class "Default")
      (node (ref "SWD") (pin "6") (pinfunction "6_6") (pintype "passive"))
      (node (ref "U1") (pin "46") (pinfunction "PA13_46") (pintype "bidirectional"))
    )
    (net (code "23") (name "NETLIGHT") (class "Default")
      (node (ref "R26") (pin "2") (pinfunction "2_2") (pintype "passive"))
      (node (ref "U6") (pin "13") (pinfunction "NETLIGHT_13") (pintype "bidirectional"))
    )
    (net (code "24") (name "NRST") (class "Default")
      (node (ref "C9") (pin "1") (pinfunction "1_1") (pintype "passive"))
      (node (ref "S2") (pin "3") (pinfunction "2_3") (pintype "passive"))
      (node (ref "SWD") (pin "2") (pinfunction "2_2") (pintype "passive"))
      (node (ref "U1") (pin "7") (pinfunction "NRST_7") (pintype "bidirectional"))
    )
    (net (code "25") (name "Net-(BOOT-Pad3)") (class "Default")
      (node (ref "BOOT") (pin "3") (pinfunction "3_3") (pintype "passive"))
      (node (ref "R7") (pin "1") (pinfunction "1_1") (pintype "passive"))
    )
    (net (code "26") (name "Net-(BOOT-Pad4)") (class "Default")
      (node (ref "BOOT") (pin "4") (pinfunction "4_4") (pintype "passive"))
      (node (ref "R8") (pin "2") (pinfunction "2_2") (pintype "passive"))
    )
    (net (code "27") (name "Net-(C1-Pad1)") (class "Default")
      (node (ref "C1") (pin "1") (pinfunction "1_1") (pintype "passive"))
      (node (ref "R3") (pin "1") (pinfunction "1_1") (pintype "passive"))
    )
    (net (code "28") (name "Net-(C11-Pad1)") (class "Default")
      (node (ref "C11") (pin "1") (pinfunction "1_1") (pintype "passive"))
      (node (ref "R10") (pin "1") (pinfunction "1_1") (pintype "passive"))
      (node (ref "X1") (pin "P$1") (pinfunction "P$1_P$1") (pintype "bidirectional"))
    )
    (net (code "29") (name "Net-(C13-Pad1)") (class "Default")
      (node (ref "C13") (pin "1") (pinfunction "1_1") (pintype "passive"))
      (node (ref "Q1") (pin "1") (pinfunction "1_1") (pintype "passive"))
      (node (ref "R9") (pin "1") (pinfunction "1_1") (pintype "passive"))
    )
    (net (code "30") (name "Net-(C31-Pad2)") (class "Default")
      (node (ref "C31") (pin "2") (pinfunction "2_2") (pintype "passive"))
      (node (ref "R25") (pin "1") (pinfunction "1_1") (pintype "passive"))
      (node (ref "RF_ANT") (pin "D") (pinfunction "D_D") (pintype "bidirectional"))
    )
    (net (code "31") (name "Net-(CHG-PadC)") (class "Default")
      (node (ref "CHG") (pin "C") (pinfunction "C_C") (pintype "passive"))
      (node (ref "R11") (pin "2") (pinfunction "2_2") (pintype "passive"))
    )
    (net (code "32") (name "Net-(L2-2)") (class "Default")
      (node (ref "L2") (pin "P$2") (pinfunction "2_P$2") (pintype "passive"))
      (node (ref "U4") (pin "1") (pinfunction "LX_1") (pintype "bidirectional"))
    )
    (net (code "33") (name "Net-(LED-PadC)") (class "Default")
      (node (ref "LED") (pin "C") (pinfunction "C_C") (pintype "passive"))
      (node (ref "R2") (pin "2") (pinfunction "2_2") (pintype "passive"))
    )
    (net (code "34") (name "Net-(MODEMCTL-Pad8)") (class "Default")
      (node (ref "MODEMCTL") (pin "8") (pinfunction "8_8") (pintype "passive"))
      (node (ref "R32") (pin "2") (pinfunction "2_2") (pintype "passive"))
    )
    (net (code "35") (name "Net-(MODEMCTL-Pad10)") (class "Default")
      (node (ref "MODEMCTL") (pin "10") (pinfunction "10_10") (pintype "passive"))
      (node (ref "R5") (pin "2") (pinfunction "2_2") (pintype "passive"))
    )
    (net (code "36") (name "Net-(NET-PadC)") (class "Default")
      (node (ref "NET") (pin "C") (pinfunction "C_C") (pintype "passive"))
      (node (ref "R28") (pin "1") (pinfunction "1_1") (pintype "passive"))
    )
    (net (code "37") (name "Net-(PWR-PadA)") (class "Default")
      (node (ref "PWR") (pin "A") (pinfunction "A_A") (pintype "passive"))
      (node (ref "R1") (pin "1") (pinfunction "1_1") (pintype "passive"))
    )
    (net (code "38") (name "Net-(Q2-B)") (class "Default")
      (node (ref "Q2") (pin "1") (pinfunction "B_1") (pintype "passive"))
      (node (ref "R33") (pin "1") (pinfunction "1_1") (pintype "passive"))
      (node (ref "R34") (pin "1") (pinfunction "1_1") (pintype "passive"))
    )
    (net (code "39") (name "Net-(Q3-B)") (class "Default")
      (node (ref "Q3") (pin "1") (pinfunction "B_1") (pintype "passive"))
      (node (ref "R19") (pin "1") (pinfunction "1_1") (pintype "passive"))
      (node (ref "R22") (pin "1") (pinfunction "1_1") (pintype "passive"))
    )
    (net (code "40") (name "Net-(Q4-B)") (class "Default")
      (node (ref "Q4") (pin "1") (pinfunction "B_1") (pintype "passive"))
      (node (ref "R20") (pin "1") (pinfunction "1_1") (pintype "passive"))
      (node (ref "R23") (pin "1") (pinfunction "1_1") (pintype "passive"))
    )
    (net (code "41") (name "Net-(Q5-B)") (class "Default")
      (node (ref "Q5") (pin "1") (pinfunction "B_1") (pintype "passive"))
      (node (ref "R26") (pin "1") (pinfunction "1_1") (pintype "passive"))
      (node (ref "R27") (pin "2") (pinfunction "2_2") (pintype "passive"))
    )
    (net (code "42") (name "Net-(Q5-C)") (class "Default")
      (node (ref "Q5") (pin "3") (pinfunction "C_3") (pintype "passive"))
      (node (ref "R28") (pin "2") (pinfunction "2_2") (pintype "passive"))
    )
    (net (code "43") (name "Net-(S1-O)") (class "Default")
      (node (ref "JP4") (pin "2") (pinfunction "2_2") (pintype "passive"))
      (node (ref "S1") (pin "1") (pinfunction "O_1") (pintype "passive"))
      (node (ref "S1") (pin "2") (pinfunction "P_2") (pintype "passive"))
    )
    (net (code "44") (name "Net-(U2-PROG)") (class "Default")
      (node (ref "R13") (pin "1") (pinfunction "1_1") (pintype "passive"))
      (node (ref "U2") (pin "5") (pinfunction "PROG_5") (pintype "input"))
    )
    (net (code "45") (name "Net-(U2-STAT)") (class "Default")
      (node (ref "R11") (pin "1") (pinfunction "1_1") (pintype "passive"))
      (node (ref "U2") (pin "1") (pinfunction "STAT_1") (pintype "output"))
    )
    (net (code "46") (name "Net-(U3-EN)") (class "Default")
      (node (ref "R12") (pin "1") (pinfunction "1_1") (pintype "passive"))
      (node (ref "U3") (pin "3") (pinfunction "EN_3") (pintype "input"))
    )
    (net (code "47") (name "Net-(U4-EN)") (class "Default")
      (node (ref "R14") (pin "2") (pinfunction "2_2") (pintype "passive"))
      (node (ref "U4") (pin "2") (pinfunction "EN_2") (pintype "bidirectional"))
    )
    (net (code "48") (name "Net-(U4-FB)") (class "Default")
      (node (ref "R15") (pin "2") (pinfunction "2_2") (pintype "passive"))
      (node (ref "R16") (pin "1") (pinfunction "1_1") (pintype "passive"))
      (node (ref "U4") (pin "5") (pinfunction "FB_5") (pintype "bidirectional"))
    )
    (net (code "49") (name "OSC32_IN") (class "Default")
      (node (ref "C12") (pin "1") (pinfunction "1_1") (pintype "passive"))
      (node (ref "Q1") (pin "2") (pinfunction "2_2") (pintype "passive"))
      (node (ref "U1") (pin "3") (pinfunction "PC14-OSC32_IN_3") (pintype "bidirectional"))
    )
    (net (code "50") (name "OSC32_OUT") (class "Default")
      (node (ref "R9") (pin "2") (pinfunction "2_2") (pintype "passive"))
      (node (ref "U1") (pin "4") (pinfunction "PC15-OSC32_OUT_4") (pintype "bidirectional"))
    )
    (net (code "51") (name "OSC_IN") (class "Default")
      (node (ref "C10") (pin "1") (pinfunction "1_1") (pintype "passive"))
      (node (ref "U1") (pin "5") (pinfunction "OSC_IN_5") (pintype "input"))
      (node (ref "X1") (pin "P$2") (pinfunction "P$2_P$2") (pintype "bidirectional"))
    )
    (net (code "52") (name "OSC_OUT") (class "Default")
      (node (ref "R10") (pin "2") (pinfunction "2_2") (pintype "passive"))
      (node (ref "U1") (pin "6") (pinfunction "OSC_OUT_6") (pintype "output"))
    )
    (net (code "53") (name "PA0") (class "Default")
      (node (ref "ANALOG") (pin "6") (pinfunction "6_6") (pintype "passive"))
      (node (ref "U1") (pin "14") (pinfunction "PA0-WKUP_14") (pintype "bidirectional"))
    )
    (net (code "54") (name "PA1") (class "Default")
      (node (ref "ANALOG") (pin "5") (pinfunction "5_5") (pintype "passive"))
      (node (ref "U1") (pin "15") (pinfunction "PA1_15") (pintype "bidirectional"))
    )
    (net (code "55") (name "PA2") (class "Default")
      (node (ref "DIGITAL") (pin "8") (pinfunction "8_8") (pintype "passive"))
      (node (ref "U1") (pin "16") (pinfunction "PA2_16") (pintype "bidirectional"))
    )
    (net (code "56") (name "PA3") (class "Default")
      (node (ref "DIGITAL") (pin "7") (pinfunction "7_7") (pintype "passive"))
      (node (ref "U1") (pin "17") (pinfunction "PA3_17") (pintype "bidirectional"))
    )
    (net (code "57") (name "PA4") (class "Default")
      (node (ref "CC1101") (pin "4") (pinfunction "4_4") (pintype "passive"))
      (node (ref "SPI1") (pin "5") (pinfunction "5_5") (pintype "passive"))
      (node (ref "U1") (pin "20") (pinfunction "PA4_20") (pintype "bidirectional"))
    )
    (net (code "58") (name "PA5") (class "Default")
      (node (ref "CC1101") (pin "7") (pinfunction "7_7") (pintype "passive"))
      (node (ref "SPI1") (pin "2") (pinfunction "2_2") (pintype "passive"))
      (node (ref "U1") (pin "21") (pinfunction "PA5_21") (pintype "bidirectional"))
    )
    (net (code "59") (name "PA6") (class "Default")
      (node (ref "CC1101") (pin "8") (pinfunction "8_8") (pintype "passive"))
      (node (ref "SPI1") (pin "3") (pinfunction "3_3") (pintype "passive"))
      (node (ref "U1") (pin "22") (pinfunction "PA6_22") (pintype "bidirectional"))
    )
    (net (code "60") (name "PA7") (class "Default")
      (node (ref "CC1101") (pin "6") (pinfunction "6_6") (pintype "passive"))
      (node (ref "SPI1") (pin "4") (pinfunction "4_4") (pintype "passive"))
      (node (ref "U1") (pin "23") (pinfunction "PA7_23") (pintype "bidirectional"))
    )
    (net (code "61") (name "PA8") (class "Default")
      (node (ref "DIGITAL") (pin "1") (pinfunction "1_1") (pintype "passive"))
      (node (ref "U1") (pin "41") (pinfunction "PA8_41") (pintype "bidirectional"))
    )
    (net (code "62") (name "PB0") (class "Default")
      (node (ref "ANALOG") (pin "4") (pinfunction "4_4") (pintype "passive"))
      (node (ref "U1") (pin "26") (pinfunction "PB0_26") (pintype "bidirectional"))
    )
    (net (code "63") (name "PB5") (class "Default")
      (node (ref "DIGITAL") (pin "4") (pinfunction "4_4") (pintype "passive"))
      (node (ref "U1") (pin "57") (pinfunction "PB5_57") (pintype "bidirectional"))
    )
    (net (code "64") (name "PB6") (class "Default")
      (node (ref "DIGITAL") (pin "6") (pinfunction "6_6") (pintype "passive"))
      (node (ref "U1") (pin "58") (pinfunction "PB6_58") (pintype "bidirectional"))
    )
    (net (code "65") (name "PB12") (class "Default")
      (node (ref "CC1101") (pin "5") (pinfunction "5_5") (pintype "passive"))
      (node (ref "SPI2") (pin "2") (pinfunction "2_2") (pintype "passive"))
      (node (ref "U1") (pin "33") (pinfunction "PB12_33") (pintype "bidirectional"))
    )
    (net (code "66") (name "PB13") (class "Default")
      (node (ref "LED") (pin "A") (pinfunction "A_A") (pintype "passive"))
      (node (ref "SPI2") (pin "5") (pinfunction "5_5") (pintype "passive"))
      (node (ref "U1") (pin "34") (pinfunction "PB13_34") (pintype "bidirectional"))
    )
    (net (code "67") (name "PB14") (class "Default")
      (node (ref "SPI2") (pin "4") (pinfunction "4_4") (pintype "passive"))
      (node (ref "U1") (pin "35") (pinfunction "PB14_35") (pintype "bidirectional"))
    )
    (net (code "68") (name "PB15") (class "Default")
      (node (ref "SPI2") (pin "3") (pinfunction "3_3") (pintype "passive"))
      (node (ref "U1") (pin "36") (pinfunction "PB15_36") (pintype "bidirectional"))
    )
    (net (code "69") (name "PC0") (class "Default")
      (node (ref "ANALOG") (pin "1") (pinfunction "1_1") (pintype "passive"))
      (node (ref "U1") (pin "8") (pinfunction "PC0_8") (pintype "bidirectional"))
    )
    (net (code "70") (name "PC1") (class "Default")
      (node (ref "ANALOG") (pin "2") (pinfunction "2_2") (pintype "passive"))
      (node (ref "U1") (pin "9") (pinfunction "PC1_9") (pintype "bidirectional"))
    )
    (net (code "71") (name "PC3") (class "Default")
      (node (ref "ANALOG") (pin "3") (pinfunction "3_3") (pintype "passive"))
      (node (ref "U1") (pin "11") (pinfunction "PC3_11") (pintype "bidirectional"))
    )
    (net (code "72") (name "PC6") (class "Default")
      (node (ref "JP2") (pin "2") (pinfunction "2_2") (pintype "passive"))
      (node (ref "U1") (pin "37") (pinfunction "PC6_37") (pintype "bidirectional"))
    )
    (net (code "73") (name "PC7") (class "Default")
      (node (ref "JP2") (pin "3") (pinfunction "3_3") (pintype "passive"))
      (node (ref "U1") (pin "38") (pinfunction "PC7_38") (pintype "bidirectional"))
    )
    (net (code "74") (name "PC8") (class "Default")
      (node (ref "JP2") (pin "4") (pinfunction "4_4") (pintype "passive"))
      (node (ref "U1") (pin "39") (pinfunction "PC8_39") (pintype "bidirectional"))
    )
    (net (code "75") (name "PC9") (class "Default")
      (node (ref "JP2") (pin "5") (pinfunction "5_5") (pintype "passive"))
      (node (ref "U1") (pin "40") (pinfunction "PC9_40") (pintype "bidirectional"))
    )
    (net (code "76") (name "PC11") (class "Default")
      (node (ref "DIGITAL") (pin "5") (pinfunction "5_5") (pintype "passive"))
      (node (ref "U1") (pin "52") (pinfunction "PC11_52") (pintype "bidirectional"))
    )
    (net (code "77") (name "PC12") (class "Default")
      (node (ref "DIGITAL") (pin "2") (pinfunction "2_2") (pintype "passive"))
      (node (ref "U1") (pin "53") (pinfunction "PC12_53") (pintype "bidirectional"))
    )
    (net (code "78") (name "PC13") (class "Default")
      (node (ref "C1") (pin "2") (pinfunction "2_2") (pintype "passive"))
      (node (ref "R4") (pin "2") (pinfunction "2_2") (pintype "passive"))
      (node (ref "S4") (pin "3") (pinfunction "2_3") (pintype "passive"))
      (node (ref "U1") (pin "2") (pinfunction "PC13_2") (pintype "bidirectional"))
    )
    (net (code "79") (name "PSM_EINT") (class "Default")
      (node (ref "MODEMCTL") (pin "2") (pinfunction "2_2") (pintype "passive"))
      (node (ref "R34") (pin "2") (pinfunction "2_2") (pintype "passive"))
    )
    (net (code "80") (name "RF_ANT") (class "Default")
      (node (ref "C29") (pin "2") (pinfunction "2_2") (pintype "passive"))
      (node (ref "R25") (pin "2") (pinfunction "2_2") (pintype "passive"))
      (node (ref "U6") (pin "39") (pinfunction "RF_ANT_39") (pintype "bidirectional"))
    )
    (net (code "81") (name "SIM1_CLK") (class "Default")
      (node (ref "D3") (pin "5") (pinfunction "C4_5") (pintype "passive"))
      (node (ref "R18") (pin "2") (pinfunction "2_2") (pintype "passive"))
      (node (ref "U6") (pin "30") (pinfunction "SIM1_CLK_30") (pintype "bidirectional"))
    )
    (net (code "82") (name "SIM1_CLK_CONN") (class "Default")
      (node (ref "C26") (pin "1") (pinfunction "1_1") (pintype "passive"))
      (node (ref "R18") (pin "1") (pinfunction "1_1") (pintype "passive"))
      (node (ref "U5") (pin "3") (pinfunction "CLK_3") (pintype "bidirectional"))
      (node (ref "U7") (pin "6") (pinfunction "CLK_6") (pintype "input"))
    )
    (net (code "83") (name "SIM1_DATA") (class "Default")
      (node (ref "D3") (pin "4") (pinfunction "C3_4") (pintype "passive"))
      (node (ref "R21") (pin "2") (pinfunction "2_2") (pintype "passive"))
      (node (ref "R24") (pin "2") (pinfunction "2_2") (pintype "passive"))
      (node (ref "U6") (pin "29") (pinfunction "SIM1_DATA_29") (pintype "bidirectional"))
    )
    (net (code "84") (name "SIM1_DATA_CONN") (class "Default")
      (node (ref "C27") (pin "2") (pinfunction "2_2") (pintype "passive"))
      (node (ref "R24") (pin "1") (pinfunction "1_1") (pintype "passive"))
      (node (ref "U5") (pin "7") (pinfunction "I/O_7") (pintype "bidirectional"))
      (node (ref "U7") (pin "3") (pinfunction "I/O_3") (pintype "bidirectional"))
    )
    (net (code "85") (name "SIM1_RST") (class "Default")
      (node (ref "D3") (pin "3") (pinfunction "C2_3") (pintype "passive"))
      (node (ref "R17") (pin "2") (pinfunction "2_2") (pintype "passive"))
      (node (ref "U6") (pin "28") (pinfunction "SIM1_RST_28") (pintype "bidirectional"))
    )
    (net (code "86") (name "SIM1_RST_CONN") (class "Default")
      (node (ref "C24") (pin "2") (pinfunction "2_2") (pintype "passive"))
      (node (ref "R17") (pin "1") (pinfunction "1_1") (pintype "passive"))
      (node (ref "U5") (pin "2") (pinfunction "RST_2") (pintype "bidirectional"))
      (node (ref "U7") (pin "7") (pinfunction "RST_7") (pintype "input"))
    )
    (net (code "87") (name "SIM1_VDD") (class "Default")
      (node (ref "C25") (pin "1") (pinfunction "1_1") (pintype "passive"))
      (node (ref "D3") (pin "1") (pinfunction "C1_1") (pintype "passive"))
      (node (ref "R21") (pin "1") (pinfunction "1_1") (pintype "passive"))
      (node (ref "U5") (pin "1") (pinfunction "VCC_1") (pintype "bidirectional"))
      (node (ref "U6") (pin "27") (pinfunction "SIM1_VDD_27") (pintype "bidirectional"))
      (node (ref "U7") (pin "8") (pinfunction "VCC_8") (pintype "power_in"))
    )
    (net (code "88") (name "STM_PSM_EINT") (class "Default")
      (node (ref "MODEMCTL") (pin "1") (pinfunction "1_1") (pintype "passive"))
      (node (ref "U1") (pin "24") (pinfunction "PC4_24") (pintype "bidirectional"))
    )
    (net (code "89") (name "STM_PWRKEY") (class "Default")
      (node (ref "MODEMCTL") (pin "3") (pinfunction "3_3") (pintype "passive"))
      (node (ref "U1") (pin "25") (pinfunction "PC5_25") (pintype "bidirectional"))
    )
    (net (code "90") (name "STM_RESET") (class "Default")
      (node (ref "MODEMCTL") (pin "5") (pinfunction "5_5") (pintype "passive"))
      (node (ref "U1") (pin "27") (pinfunction "PB1_27") (pintype "bidirectional"))
    )
    (net (code "91") (name "STM_RX") (class "Default")
      (node (ref "MODEMCTL") (pin "7") (pinfunction "7_7") (pintype "passive"))
      (node (ref "U1") (pin "30") (pinfunction "PB11_30") (pintype "bidirectional"))
    )
    (net (code "92") (name "STM_TX") (class "Default")
      (node (ref "MODEMCTL") (pin "9") (pinfunction "9_9") (pintype "passive"))
      (node (ref "U1") (pin "29") (pinfunction "PB10_29") (pintype "bidirectional"))
    )
    (net (code "93") (name "USART1_RX") (class "Default")
      (node (ref "U1") (pin "43") (pinfunction "PA10_43") (pintype "bidirectional"))
      (node (ref "USART1") (pin "2") (pinfunction "2_2") (pintype "passive"))
    )
    (net (code "94") (name "USART1_TX") (class "Default")
      (node (ref "U1") (pin "42") (pinfunction "PA9_42") (pintype "bidirectional"))
      (node (ref "USART1") (pin "3") (pinfunction "3_3") (pintype "passive"))
    )
    (net (code "95") (name "USB_CONN_D_N") (class "Default")
      (node (ref "POWER") (pin "D-") (pinfunction "D-_D-") (pintype "bidirectional"))
      (node (ref "U8") (pin "1") (pinfunction "I/O1_2_1") (pintype "bidirectional"))
    )
    (net (code "96") (name "USB_CONN_D_P") (class "Default")
      (node (ref "POWER") (pin "D+") (pinfunction "D+_D+") (pintype "bidirectional"))
      (node (ref "U8") (pin "3") (pinfunction "I/O2_2_3") (pintype "bidirectional"))
    )
    (net (code "97") (name "USB_D_N") (class "Default")
      (node (ref "CAN") (pin "3") (pinfunction "3_3") (pintype "passive"))
      (node (ref "U1") (pin "44") (pinfunction "PA11_44") (pintype "bidirectional"))
      (node (ref "U8") (pin "6") (pinfunction "I/O1_6") (pintype "bidirectional"))
    )
    (net (code "98") (name "USB_D_P") (class "Default")
      (node (ref "CAN") (pin "2") (pinfunction "2_2") (pintype "passive"))
      (node (ref "R31") (pin "2") (pinfunction "2_2") (pintype "passive"))
      (node (ref "U1") (pin "45") (pinfunction "PA12_45") (pintype "bidirectional"))
      (node (ref "U8") (pin "4") (pinfunction "I/O2_4") (pintype "bidirectional"))
    )
    (net (code "99") (name "V+") (class "Default")
      (node (ref "C15") (pin "2") (pinfunction "2_2") (pintype "passive"))
      (node (ref "C19") (pin "+") (pinfunction "+_+") (pintype "passive"))
      (node (ref "C20") (pin "2") (pinfunction "2_2") (pintype "passive"))
      (node (ref "C30") (pin "2") (pinfunction "2_2") (pintype "passive"))
      (node (ref "C32") (pin "2") (pinfunction "2_2") (pintype "passive"))
      (node (ref "C33") (pin "2") (pinfunction "2_2") (pintype "passive"))
      (node (ref "D4") (pin "C") (pinfunction "C_C") (pintype "passive"))
      (node (ref "L2") (pin "P$1") (pinfunction "1_P$1") (pintype "passive"))
      (node (ref "NET") (pin "A") (pinfunction "A_A") (pintype "passive"))
      (node (ref "R12") (pin "2") (pinfunction "2_2") (pintype "passive"))
      (node (ref "R14") (pin "1") (pinfunction "1_1") (pintype "passive"))
      (node (ref "S1") (pin "3") (pinfunction "S_3") (pintype "passive"))
      (node (ref "U3") (pin "1") (pinfunction "IN_1") (pintype "power_in"))
      (node (ref "U4") (pin "3") (pinfunction "VIN_3") (pintype "bidirectional"))
      (node (ref "U6") (pin "33") (pinfunction "VBAT_33") (pintype "bidirectional"))
      (node (ref "U6") (pin "34") (pinfunction "VBAT_34") (pintype "bidirectional"))
    )
    (net (code "100") (name "VBUS") (class "Default")
      (node (ref "C14") (pin "2") (pinfunction "2_2") (pintype "passive"))
      (node (ref "CHG") (pin "A") (pinfunction "A_A") (pintype "passive"))
      (node (ref "F1") (pin "1") (pinfunction "1_1") (pintype "passive"))
      (node (ref "POWER-PINS") (pin "4") (pinfunction "4_4") (pintype "passive"))
      (node (ref "POWER-PINS1") (pin "4") (pinfunction "4_4") (pintype "passive"))
      (node (ref "U2") (pin "4") (pinfunction "VDD_4") (pintype "power_in"))
      (node (ref "U8") (pin "5") (pinfunction "VBUS_5") (pintype "power_in"))
      (node (ref "USART1") (pin "4") (pinfunction "4_4") (pintype "passive"))
    )
    (net (code "101") (name "VDD") (class "Default")
      (node (ref "C2") (pin "2") (pinfunction "2_2") (pintype "passive"))
      (node (ref "C3") (pin "2") (pinfunction "2_2") (pintype "passive"))
      (node (ref "L1") (pin "1") (pinfunction "1_1") (pintype "passive"))
      (node (ref "U1") (pin "13") (pinfunction "VDDA_13") (pintype "power_in"))
    )
    (net (code "102") (name "VIN") (class "Default")
      (node (ref "F1") (pin "2") (pinfunction "2_2") (pintype "passive"))
      (node (ref "POWER") (pin "VBUS") (pinfunction "VBUS_VBUS") (pintype "power_in"))
      (node (ref "U$1") (pin "PWR2") (pinfunction "TIP_PWR2") (pintype "bidirectional"))
    )
    (net (code "103") (name "unconnected-(CC1101-Pad3)") (class "Default")
      (node (ref "CC1101") (pin "3") (pinfunction "3_3") (pintype "passive"))
    )
    (net (code "104") (name "unconnected-(CC1101-Pad9)") (class "Default")
      (node (ref "CC1101") (pin "9") (pinfunction "9_9") (pintype "passive"))
    )
    (net (code "105") (name "unconnected-(D3-C5-Pad6)") (class "Default")
      (node (ref "D3") (pin "6") (pinfunction "C5_6") (pintype "passive"))
    )
    (net (code "106") (name "unconnected-(POWER-PadID)") (class "Default")
      (node (ref "POWER") (pin "ID") (pinfunction "ID_ID") (pintype "bidirectional"))
    )
    (net (code "107") (name "unconnected-(U1A-PB7-Pad59)") (class "Default")
      (node (ref "U1") (pin "59") (pinfunction "PB7_59") (pintype "bidirectional"))
    )
    (net (code "108") (name "unconnected-(U1A-PC2-Pad10)") (class "Default")
      (node (ref "U1") (pin "10") (pinfunction "PC2_10") (pintype "bidirectional"))
    )
    (net (code "109") (name "unconnected-(U1A-PC10-Pad51)") (class "Default")
      (node (ref "U1") (pin "51") (pinfunction "PC10_51") (pintype "bidirectional"))
    )
    (net (code "110") (name "unconnected-(U1A-PD2-Pad54)") (class "Default")
      (node (ref "U1") (pin "54") (pinfunction "PD2_54") (pintype "bidirectional"))
    )
    (net (code "111") (name "unconnected-(U3-P4-Pad4)") (class "Default")
      (node (ref "U3") (pin "4") (pinfunction "P4_4") (pintype "bidirectional"))
    )
    (net (code "112") (name "unconnected-(U4-RSET-Pad6)") (class "Default")
      (node (ref "U4") (pin "6") (pinfunction "RSET_6") (pintype "bidirectional"))
    )
    (net (code "113") (name "unconnected-(U5-VPP-Pad6)") (class "Default")
      (node (ref "U5") (pin "6") (pinfunction "VPP_6") (pintype "bidirectional"))
    )
    (net (code "114") (name "unconnected-(U6-ADC-Pad2)") (class "Default")
      (node (ref "U6") (pin "2") (pinfunction "ADC_2") (pintype "bidirectional"))
    )
    (net (code "115") (name "unconnected-(U6-CTS-Pad23)") (class "Default")
      (node (ref "U6") (pin "23") (pinfunction "CTS_23") (pintype "bidirectional"))
    )
    (net (code "116") (name "unconnected-(U6-RESERVED-Pad3)") (class "Default")
      (node (ref "U6") (pin "3") (pinfunction "RESERVED_3") (pintype "bidirectional"))
    )
    (net (code "117") (name "unconnected-(U6-RESERVED-Pad4)") (class "Default")
      (node (ref "U6") (pin "4") (pinfunction "RESERVED_4") (pintype "bidirectional"))
    )
    (net (code "118") (name "unconnected-(U6-RESERVED-Pad5)") (class "Default")
      (node (ref "U6") (pin "5") (pinfunction "RESERVED_5") (pintype "bidirectional"))
    )
    (net (code "119") (name "unconnected-(U6-RESERVED-Pad6)") (class "Default")
      (node (ref "U6") (pin "6") (pinfunction "RESERVED_6") (pintype "bidirectional"))
    )
    (net (code "120") (name "unconnected-(U6-RESERVED-Pad7)") (class "Default")
      (node (ref "U6") (pin "7") (pinfunction "RESERVED_7") (pintype "bidirectional"))
    )
    (net (code "121") (name "unconnected-(U6-RESERVED-Pad8)") (class "Default")
      (node (ref "U6") (pin "8") (pinfunction "RESERVED_8") (pintype "bidirectional"))
    )
    (net (code "122") (name "unconnected-(U6-RESERVED-Pad9)") (class "Default")
      (node (ref "U6") (pin "9") (pinfunction "RESERVED_9") (pintype "bidirectional"))
    )
    (net (code "123") (name "unconnected-(U6-RESERVED-Pad12)") (class "Default")
      (node (ref "U6") (pin "12") (pinfunction "RESERVED_12") (pintype "bidirectional"))
    )
    (net (code "124") (name "unconnected-(U6-RESERVED-Pad32)") (class "Default")
      (node (ref "U6") (pin "32") (pinfunction "RESERVED_32") (pintype "bidirectional"))
    )
    (net (code "125") (name "unconnected-(U6-RESERVED-Pad41)") (class "Default")
      (node (ref "U6") (pin "41") (pinfunction "RESERVED_41") (pintype "bidirectional"))
    )
    (net (code "126") (name "unconnected-(U6-RESERVED-Pad42)") (class "Default")
      (node (ref "U6") (pin "42") (pinfunction "RESERVED_42") (pintype "bidirectional"))
    )
    (net (code "127") (name "unconnected-(U6-RESERVED-Pad43)") (class "Default")
      (node (ref "U6") (pin "43") (pinfunction "RESERVED_43") (pintype "bidirectional"))
    )
    (net (code "128") (name "unconnected-(U6-RESERVED-Pad44)") (class "Default")
      (node (ref "U6") (pin "44") (pinfunction "RESERVED_44") (pintype "bidirectional"))
    )
    (net (code "129") (name "unconnected-(U6-RESERVED-Pad46)") (class "Default")
      (node (ref "U6") (pin "46") (pinfunction "RESERVED_46") (pintype "bidirectional"))
    )
    (net (code "130") (name "unconnected-(U6-RESERVED-Pad47)") (class "Default")
      (node (ref "U6") (pin "47") (pinfunction "RESERVED_47") (pintype "bidirectional"))
    )
    (net (code "131") (name "unconnected-(U6-RESERVED-Pad49)") (class "Default")
      (node (ref "U6") (pin "49") (pinfunction "RESERVED_49") (pintype "bidirectional"))
    )
    (net (code "132") (name "unconnected-(U6-RI-Pad26)") (class "Default")
      (node (ref "U6") (pin "26") (pinfunction "RI_26") (pintype "bidirectional"))
    )
    (net (code "133") (name "unconnected-(U6-RTS-Pad24)") (class "Default")
      (node (ref "U6") (pin "24") (pinfunction "RTS_24") (pintype "bidirectional"))
    )
    (net (code "134") (name "unconnected-(U6-SIM2_CLK-Pad17)") (class "Default")
      (node (ref "U6") (pin "17") (pinfunction "SIM2_CLK_17") (pintype "bidirectional"))
    )
    (net (code "135") (name "unconnected-(U6-SIM2_DATA-Pad16)") (class "Default")
      (node (ref "U6") (pin "16") (pinfunction "SIM2_DATA_16") (pintype "bidirectional"))
    )
    (net (code "136") (name "unconnected-(U6-SIM2_RST-Pad25)") (class "Default")
      (node (ref "U6") (pin "25") (pinfunction "SIM2_RST_25") (pintype "bidirectional"))
    )
    (net (code "137") (name "unconnected-(U6-SIM2_VDD-Pad18)") (class "Default")
      (node (ref "U6") (pin "18") (pinfunction "SIM2_VDD_18") (pintype "bidirectional"))
    )
    (net (code "138") (name "unconnected-(U6-VDD_EXT-Pad19)") (class "Default")
      (node (ref "U6") (pin "19") (pinfunction "VDD_EXT_19") (pintype "bidirectional"))
    )
    (net (code "139") (name "unconnected-(U7-EPAD-Pad9)") (class "Default")
      (node (ref "U7") (pin "9") (pinfunction "EPAD_9") (pintype "passive"))
    )
  )
)
